# v2_2.net
KiCad netlist of a schematic drawn in EasyEDA Pro
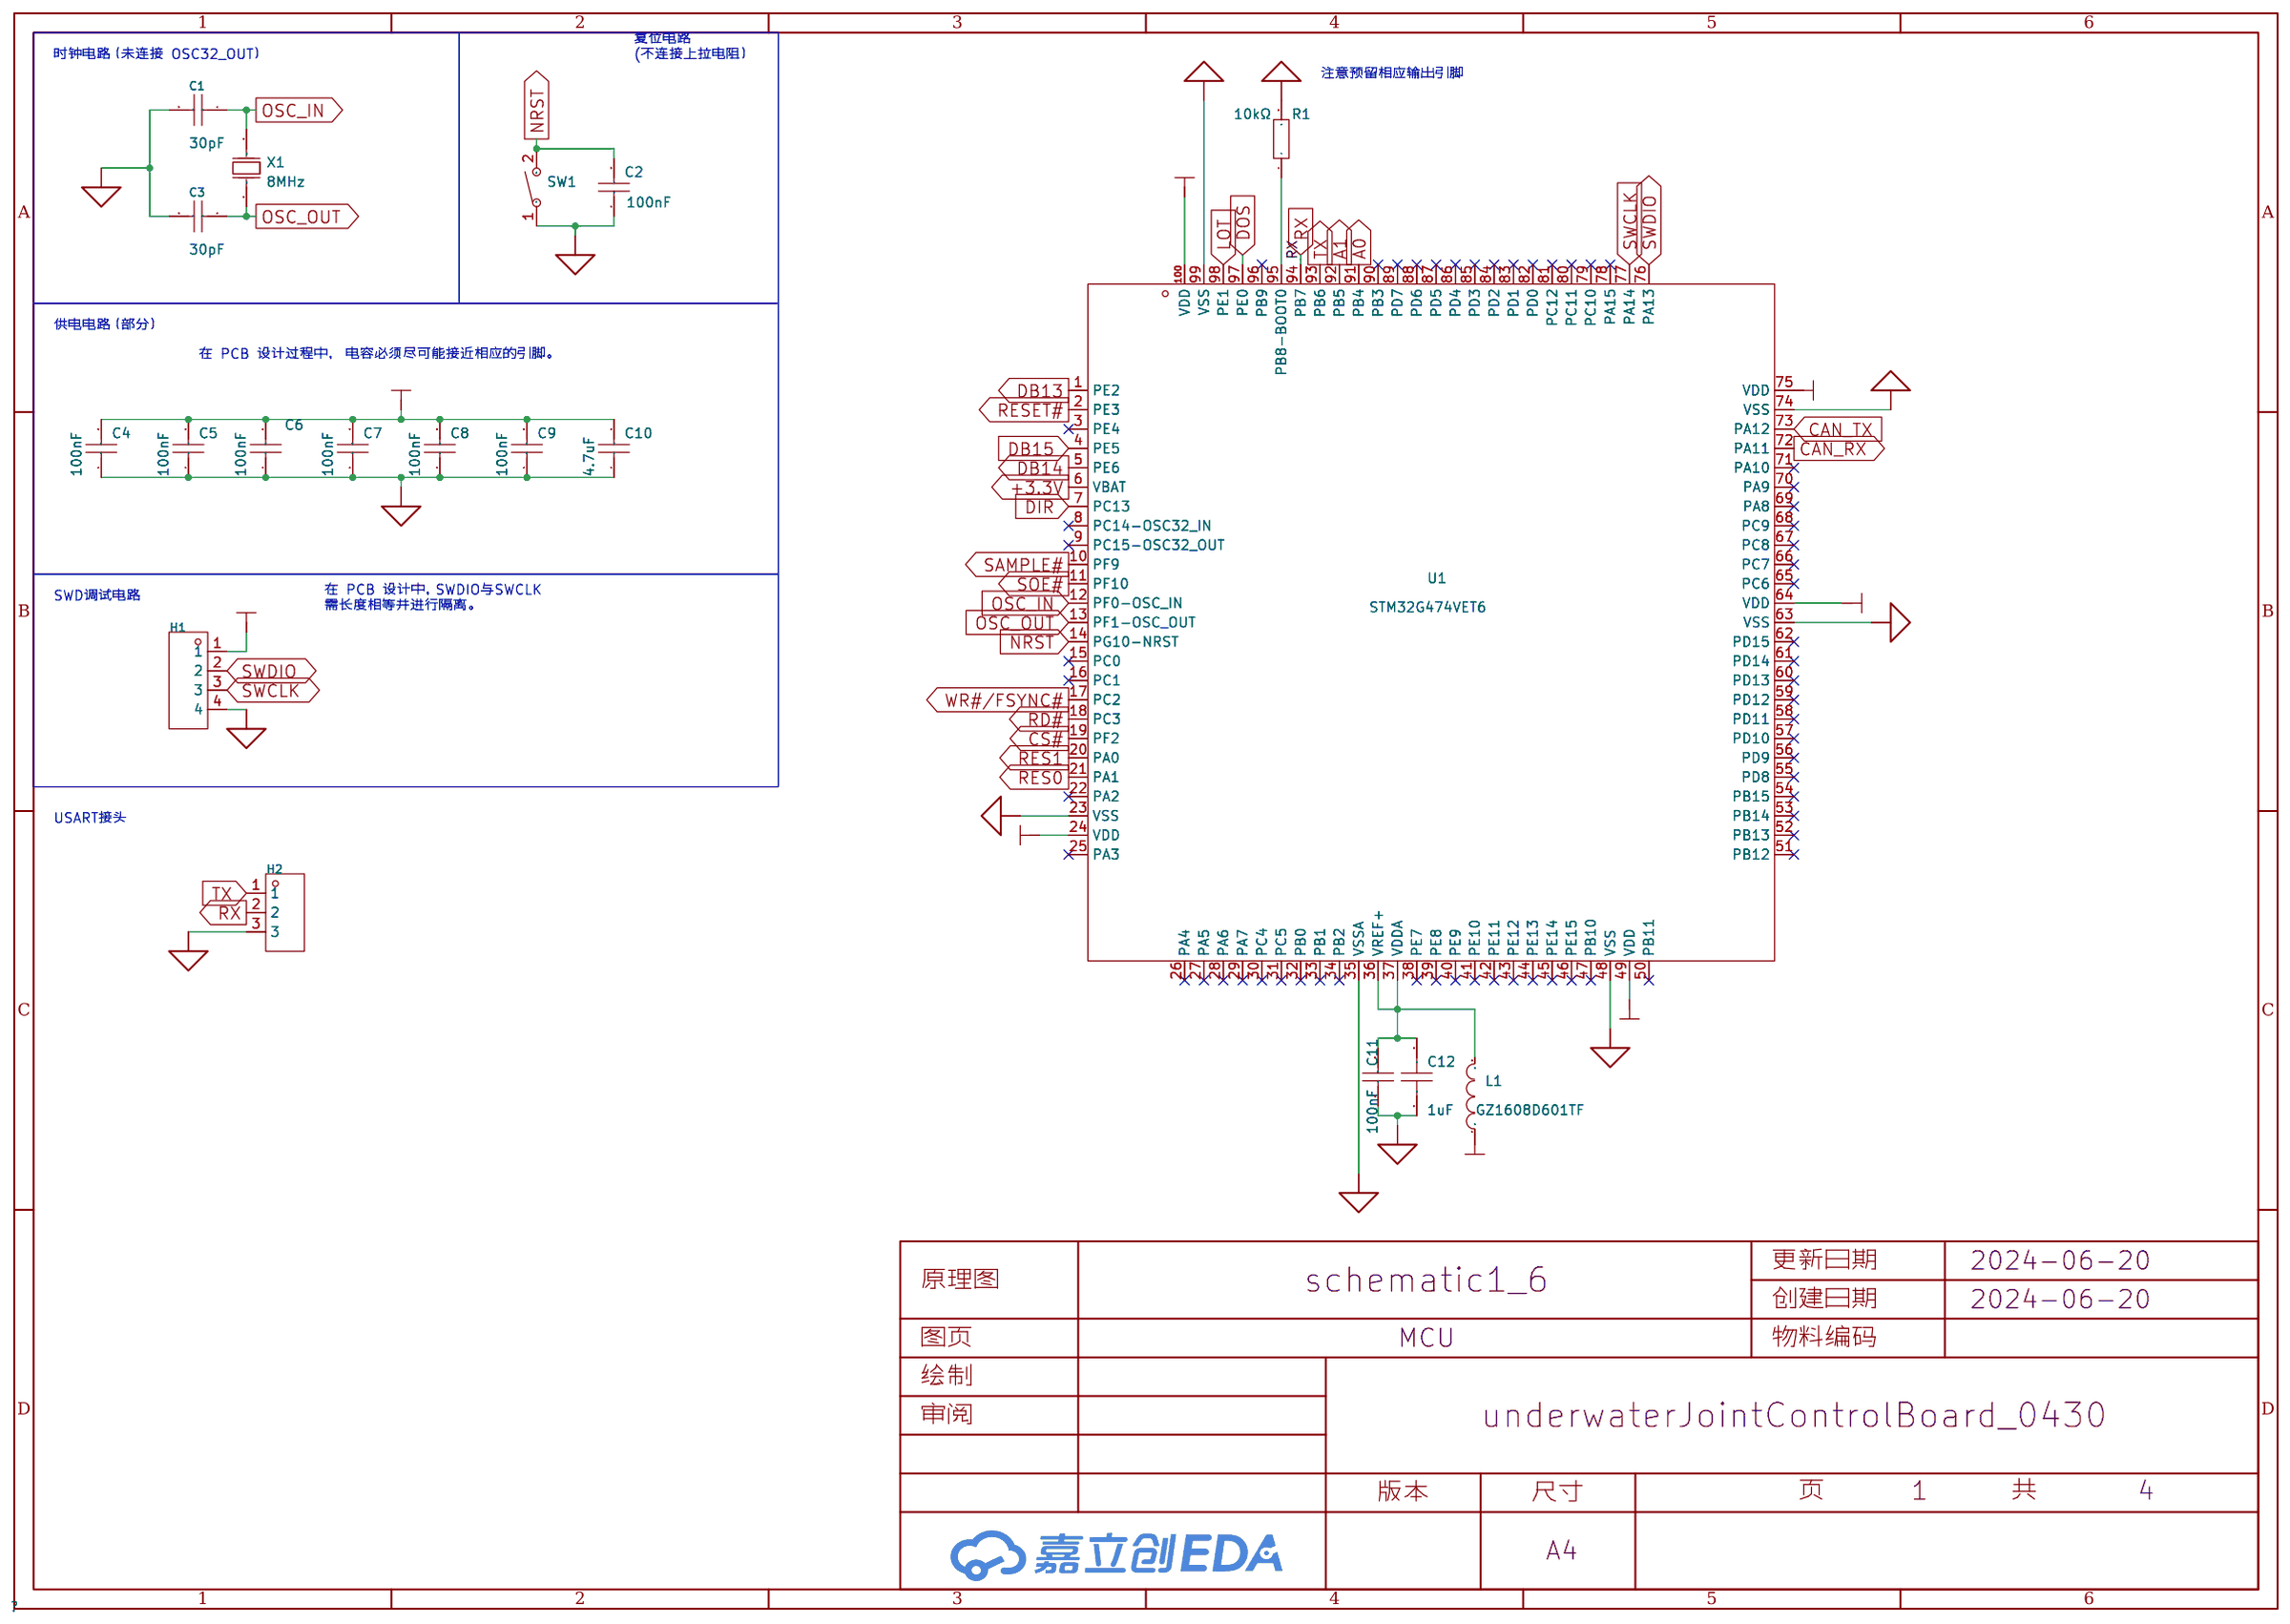
[diagram p0: MCU]
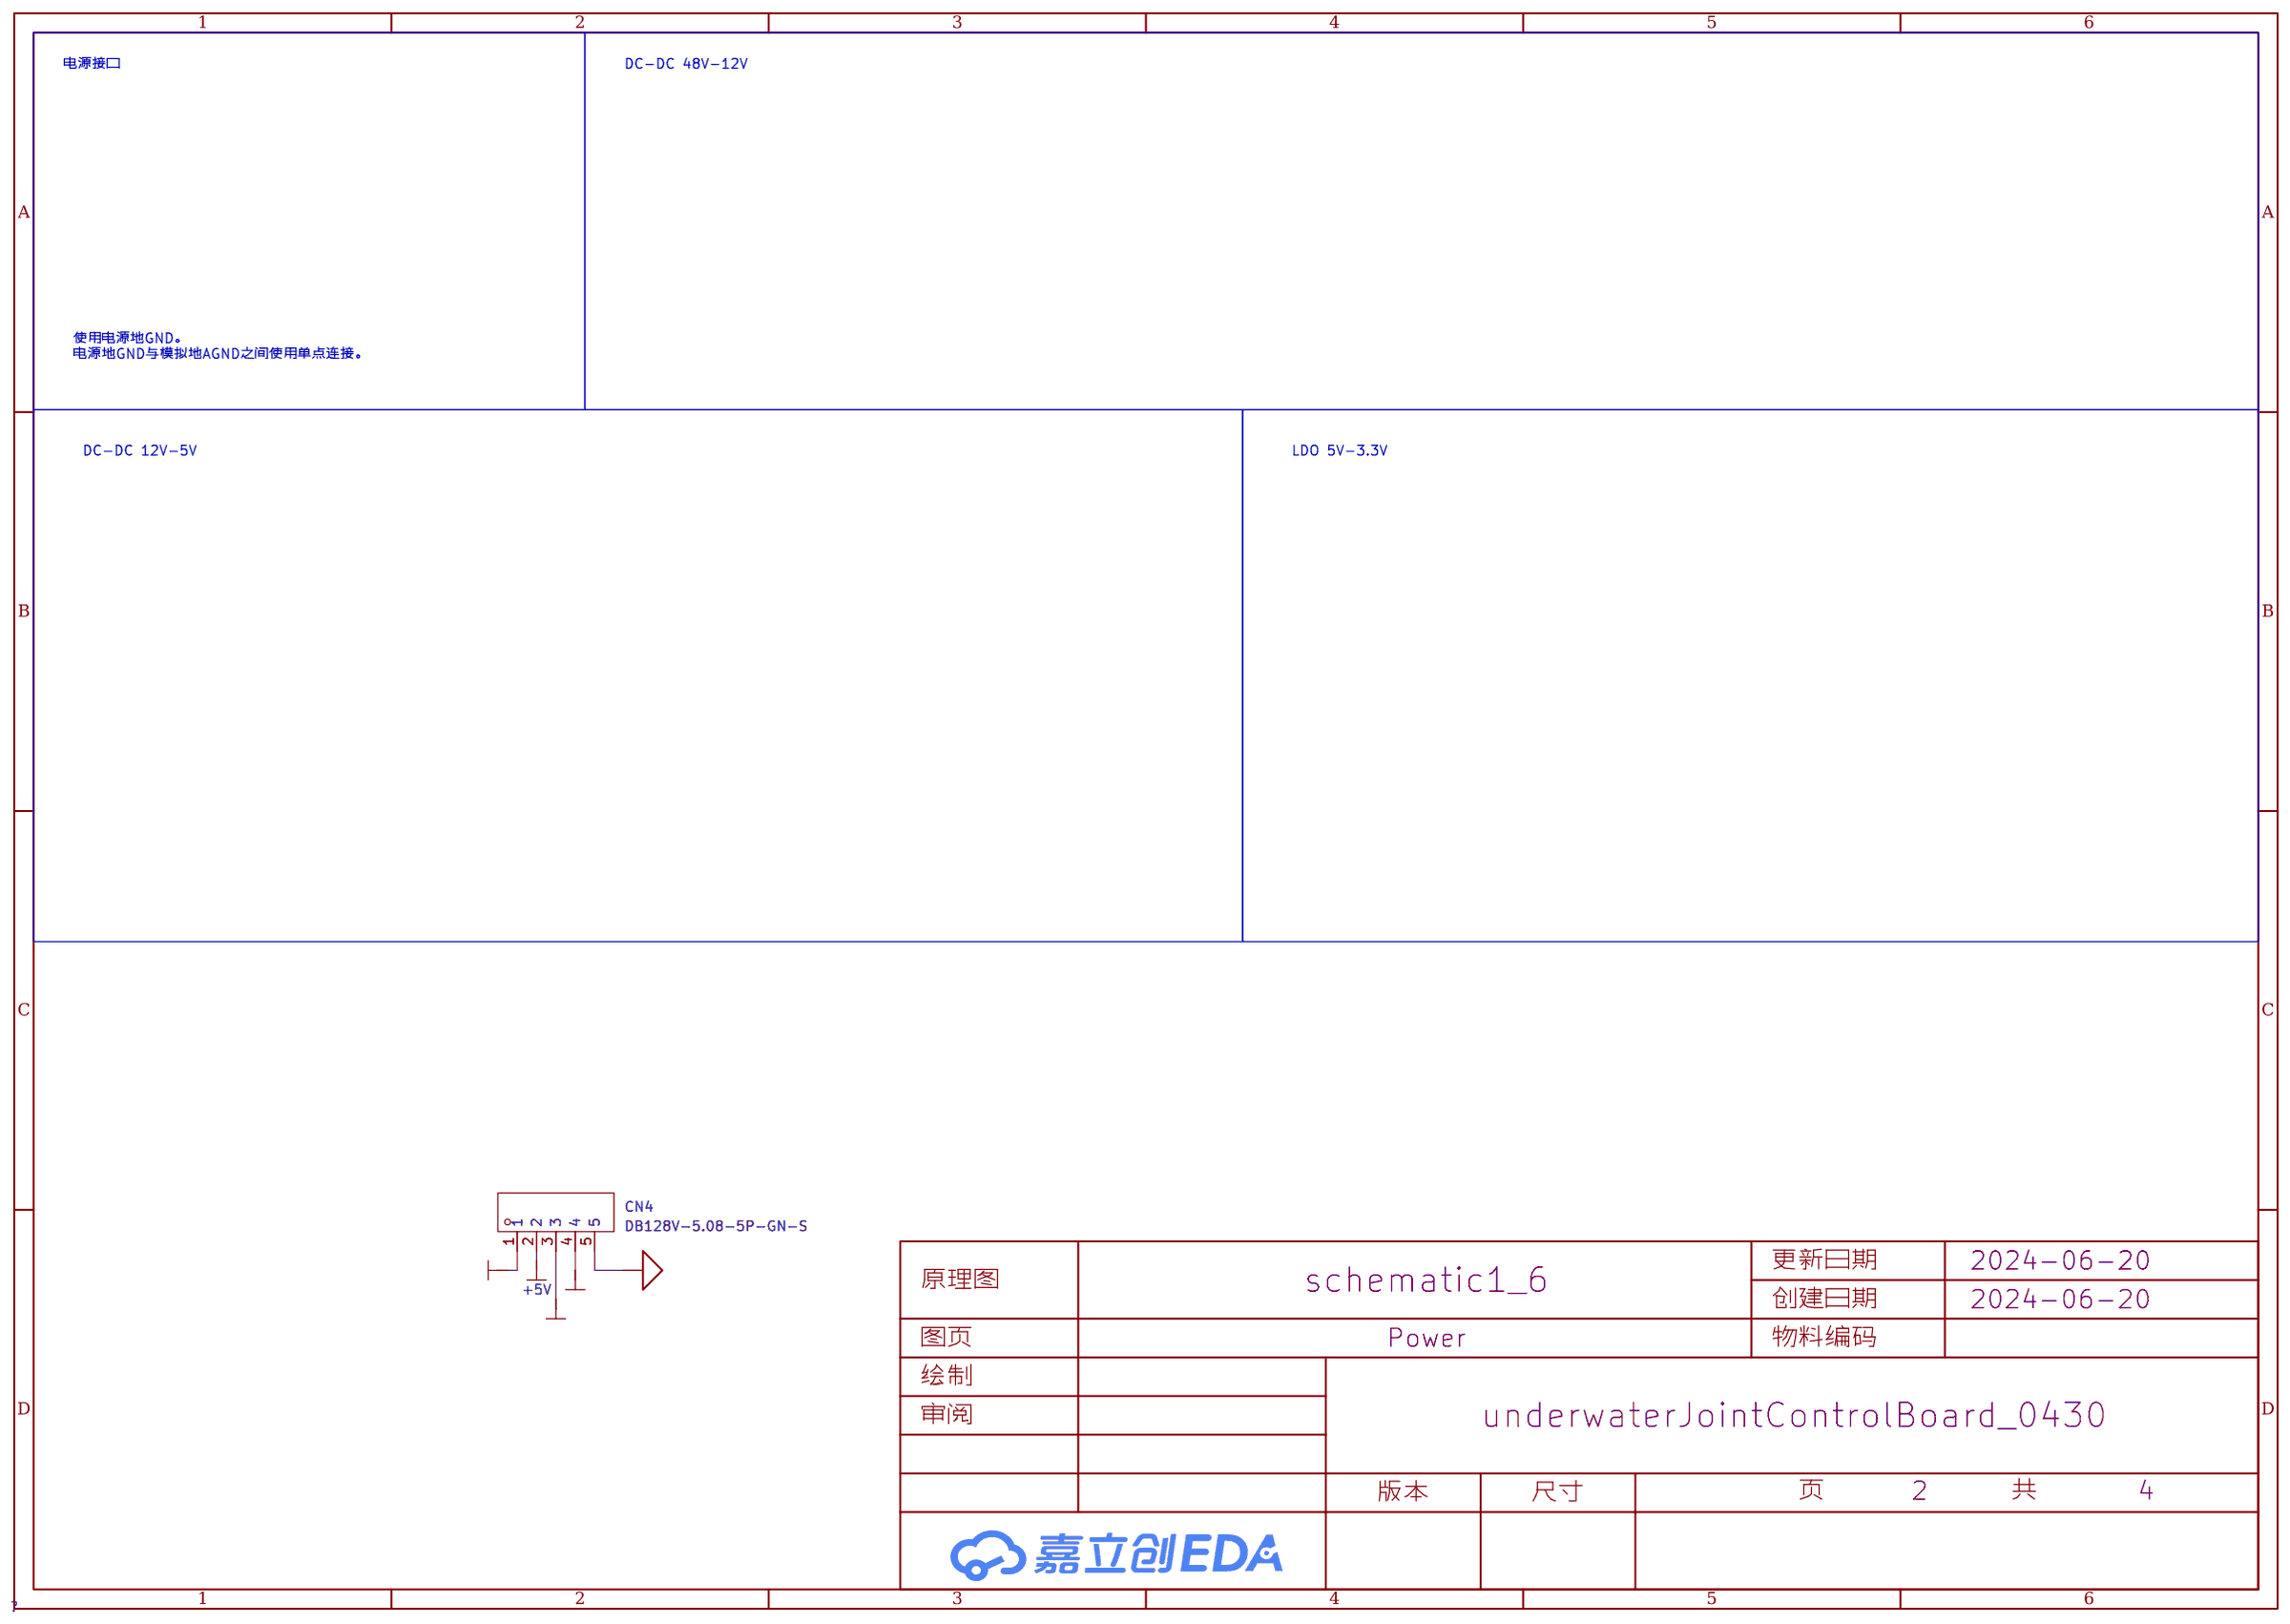
[diagram p1: Power]
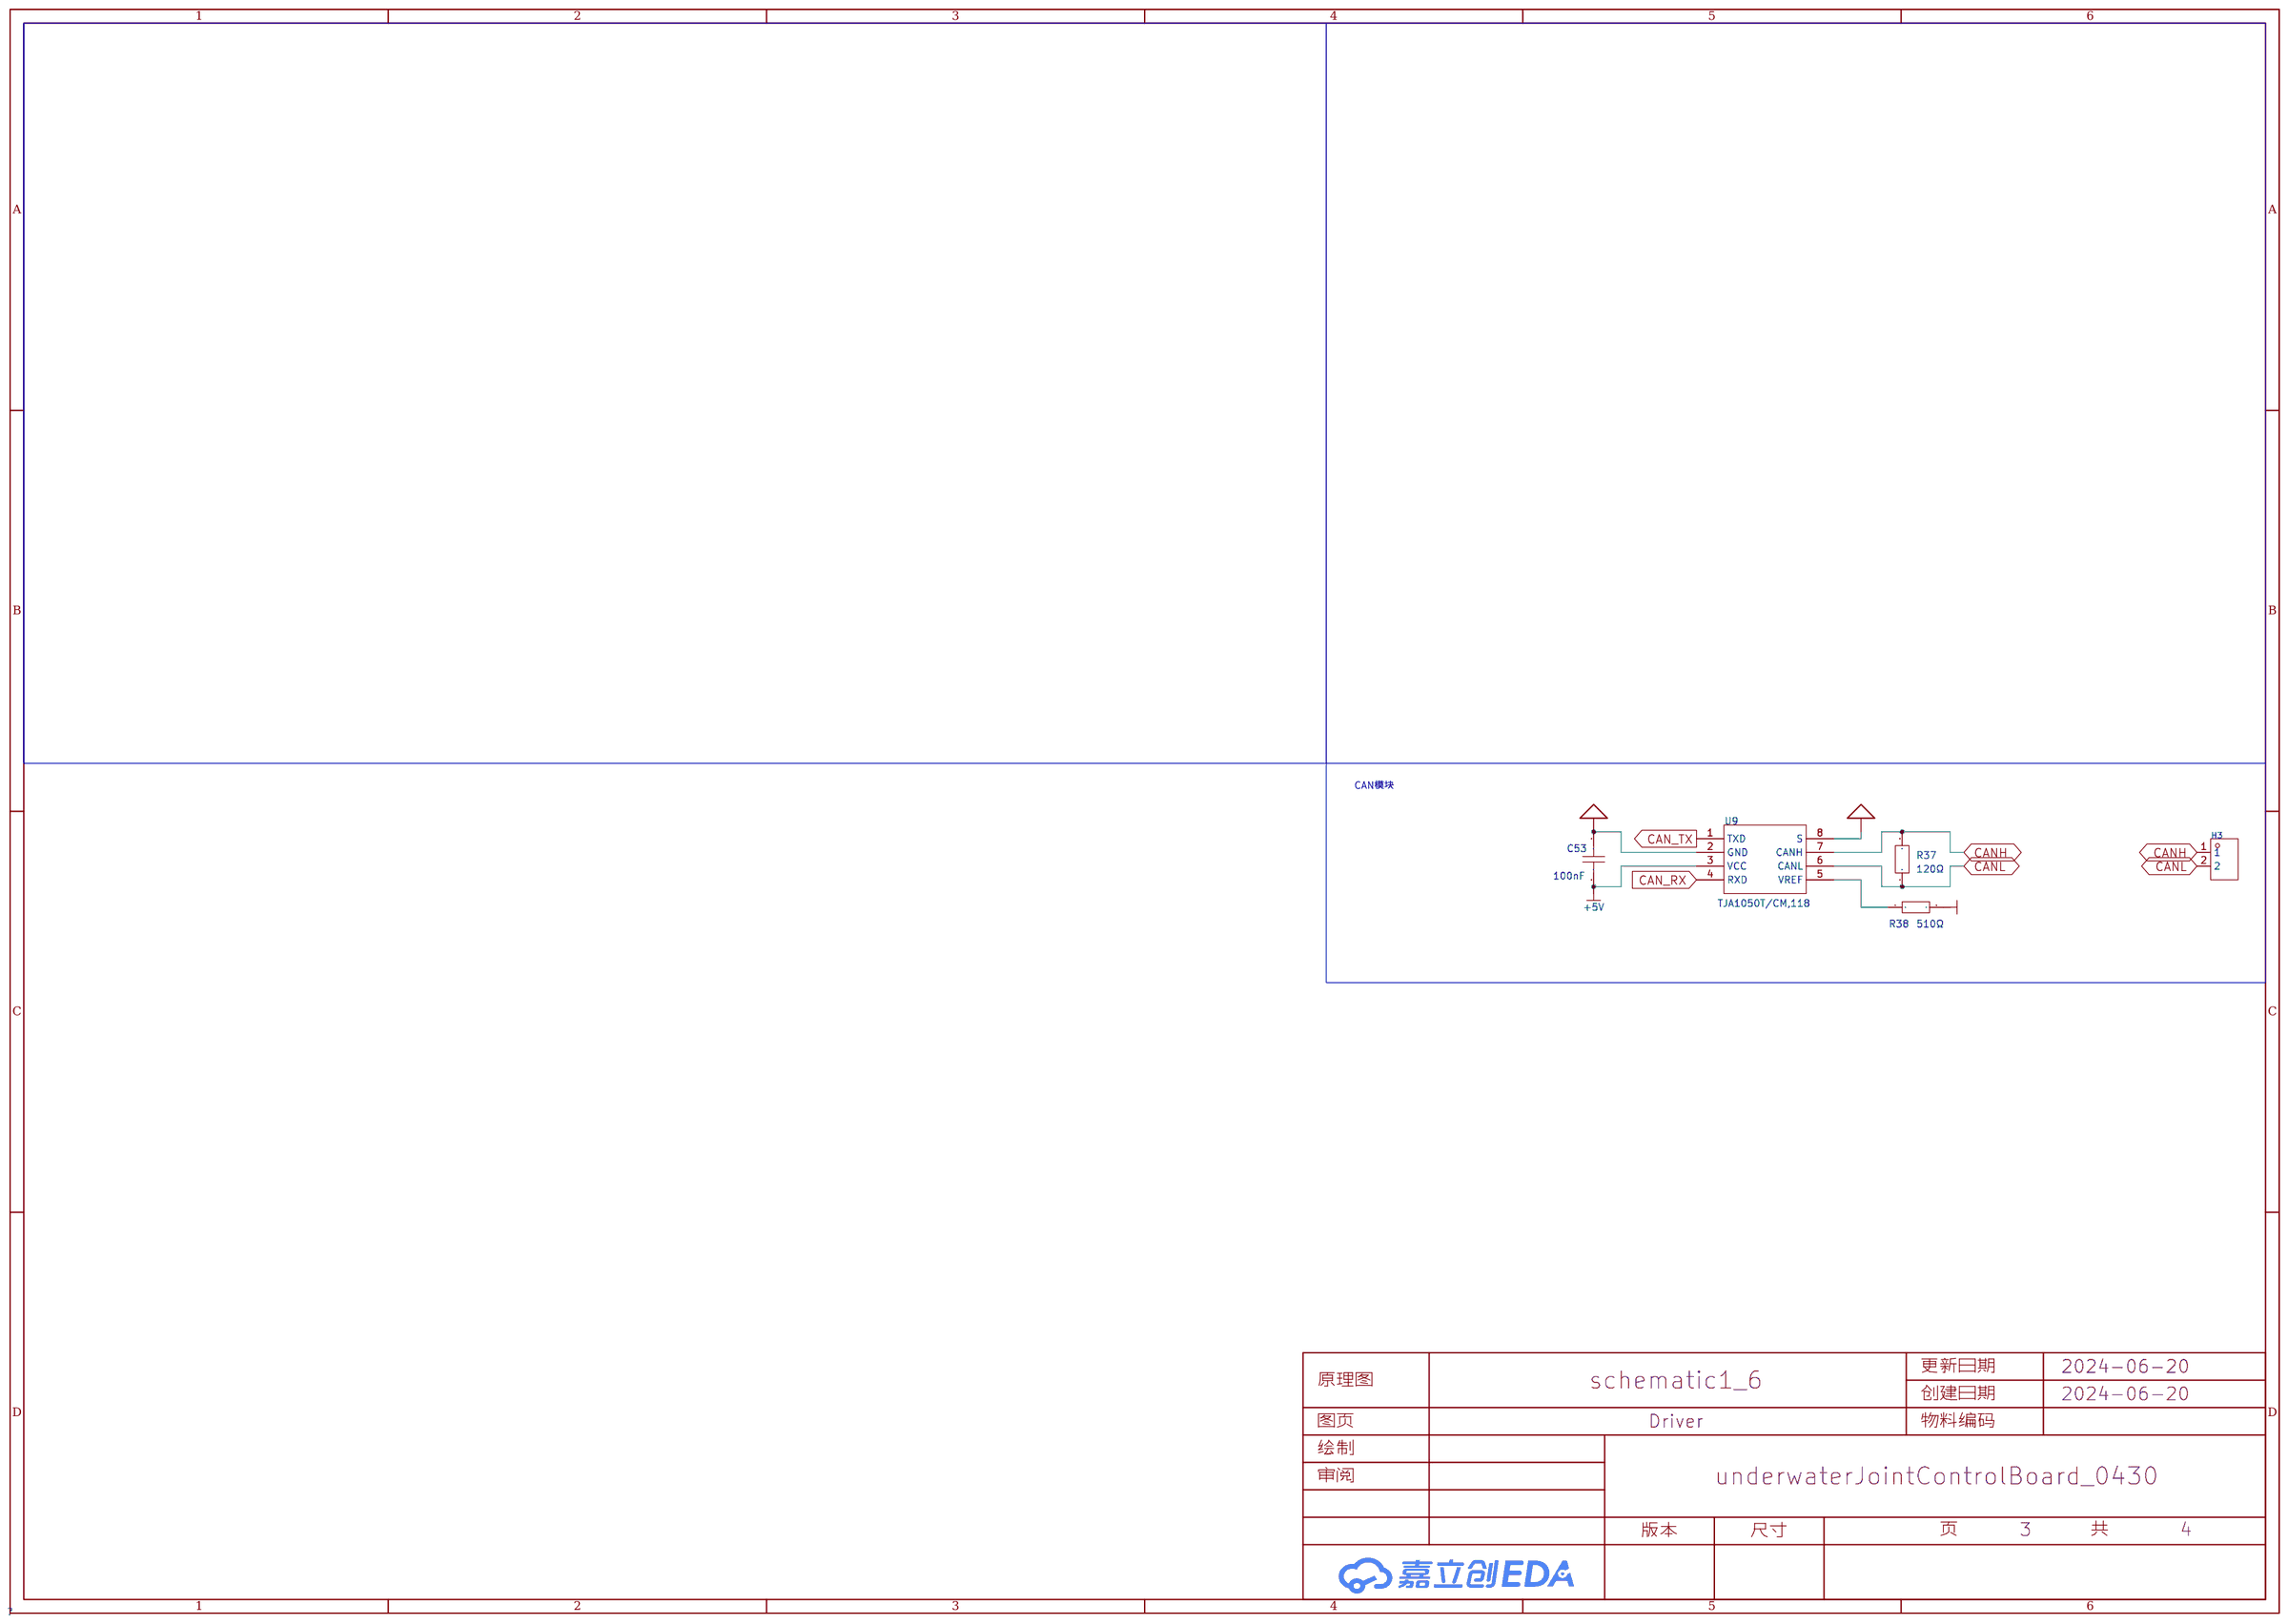
[diagram p2: Driver]
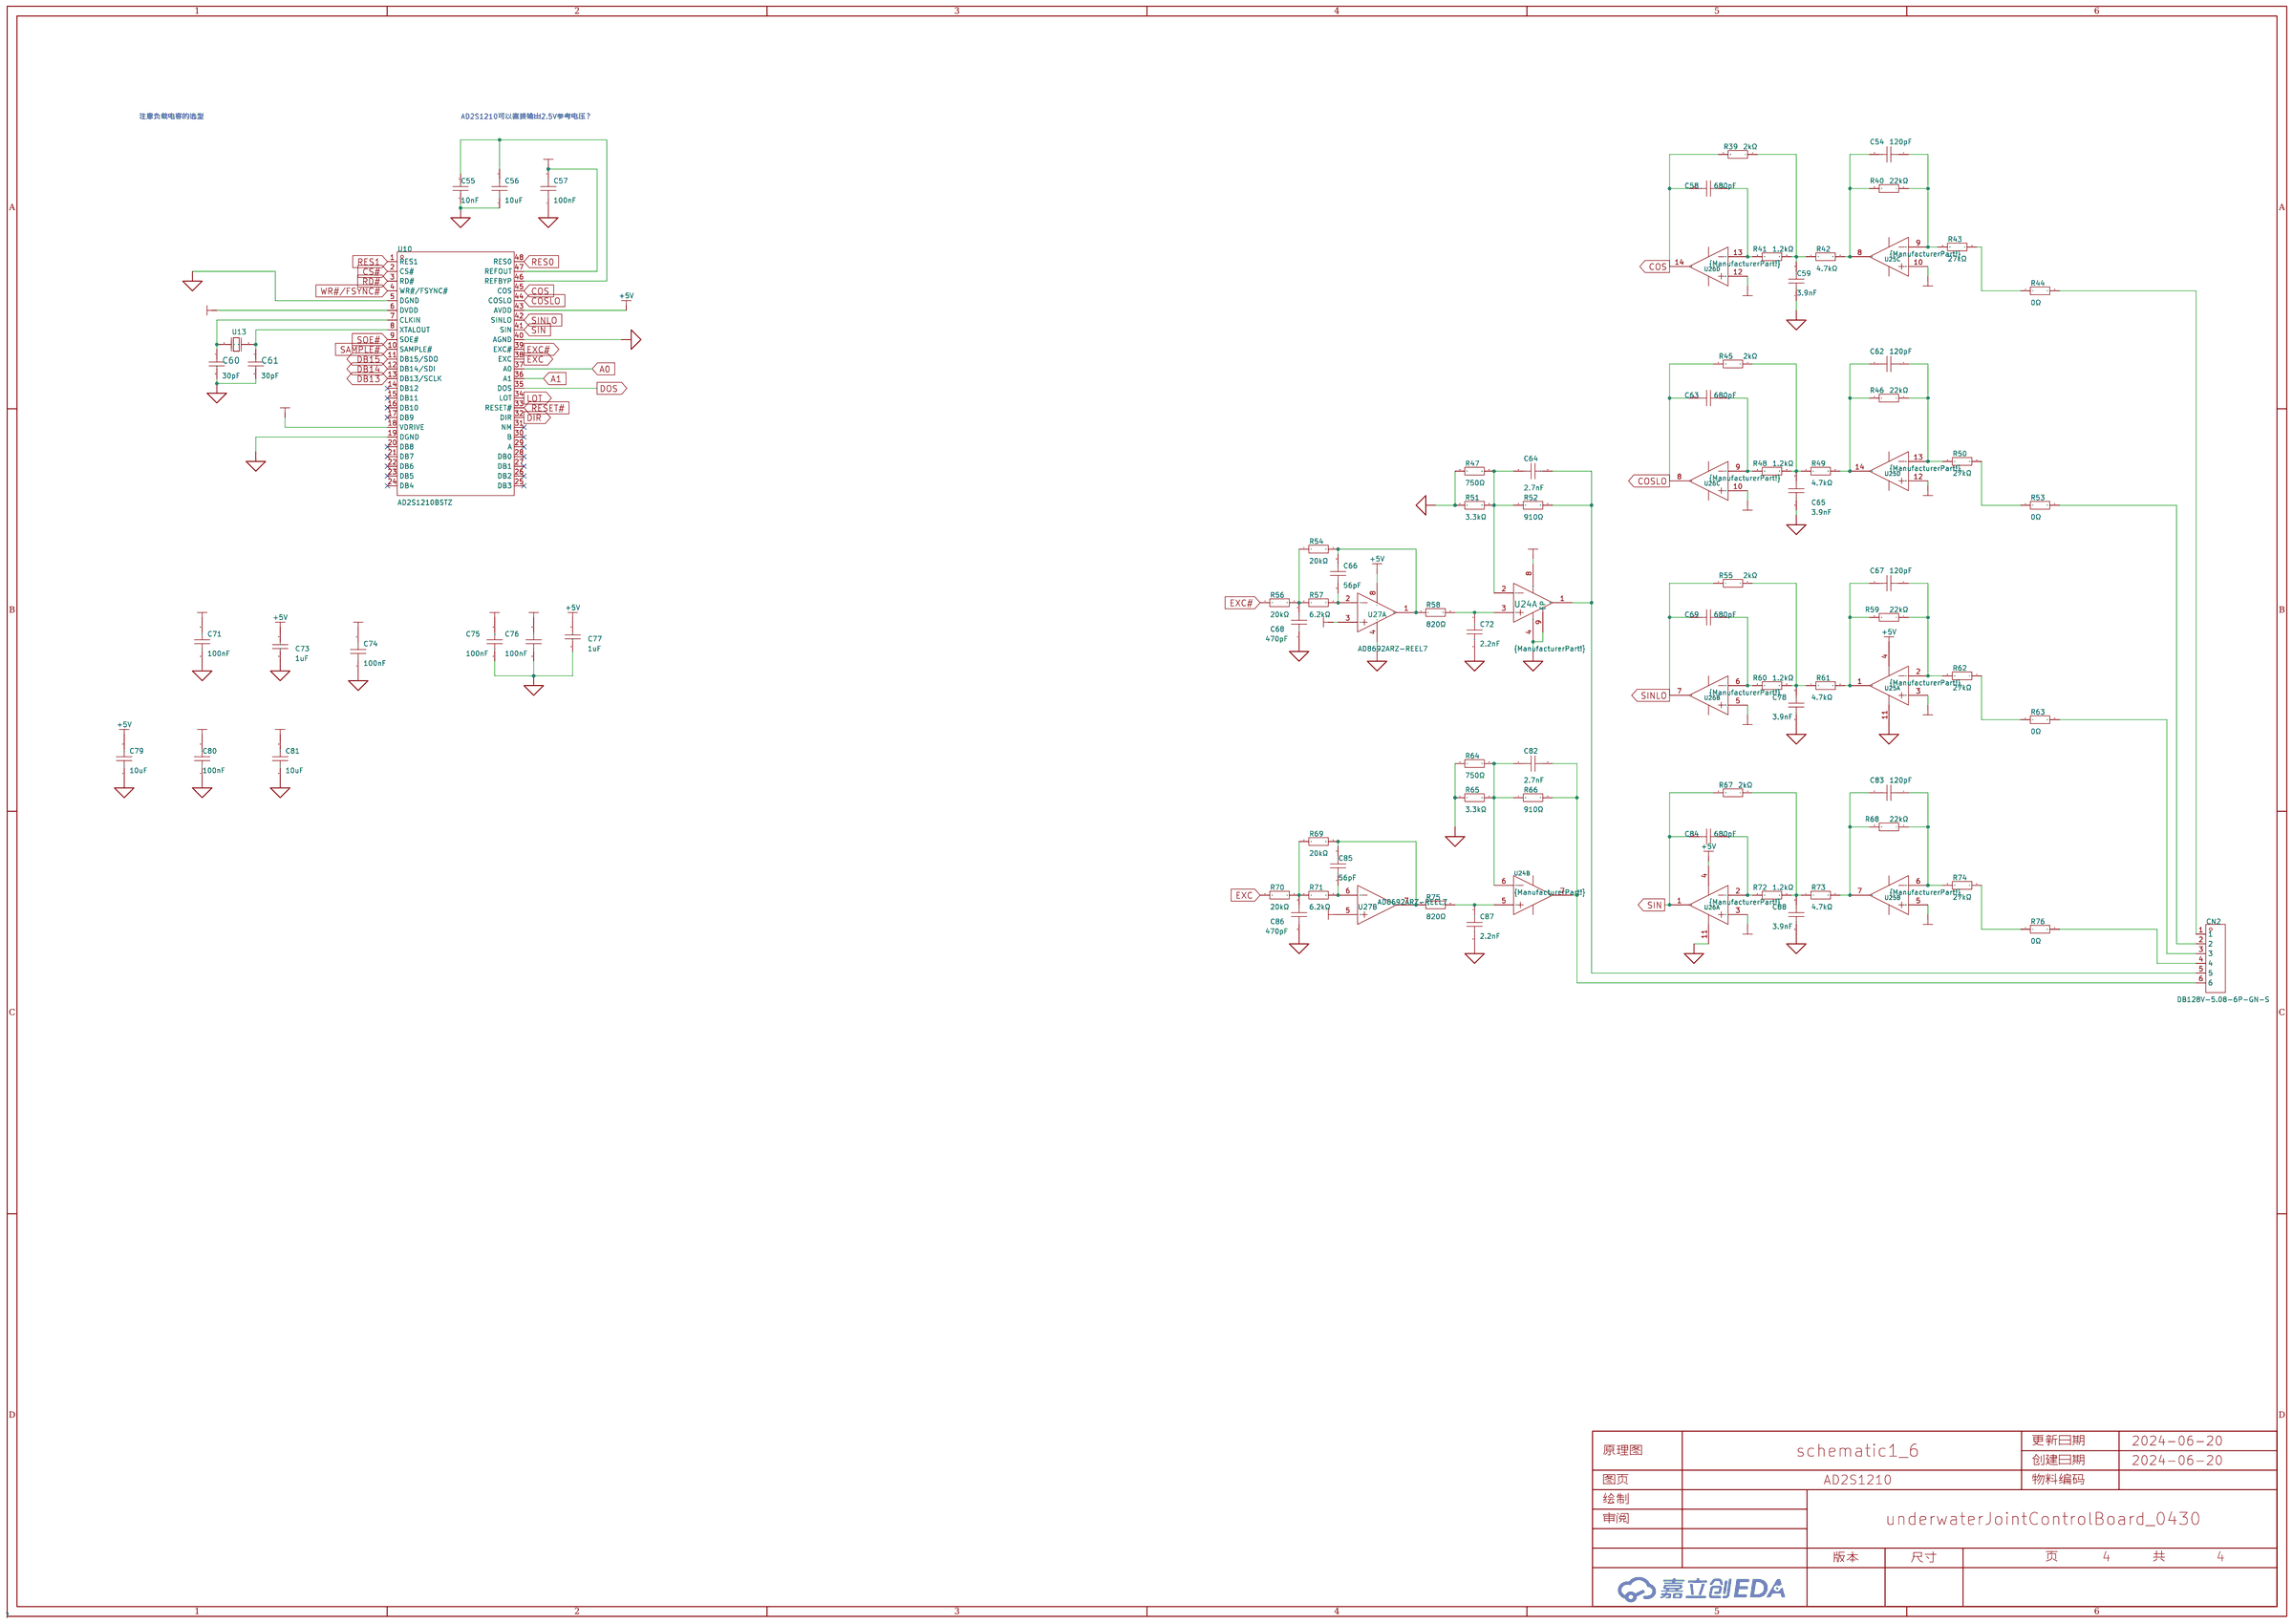
[diagram p3: AD2S1210]

(export (version "E")
  (design (tool "Eeschema 10.0.6"))
  (components
    (comp (ref "C1")
      (value "30pF")
      (footprint "easyedapro:C0402")
      (description "容值:30pF;精度:±5%;额定电压:50V;材质(温度系数):C0G;")
      (fields (field (name "Manufacturer Part") "0402CG300J500NT") (field (name "Manufacturer") "FH(风华)"))
      (libsource (lib "easyedapro") (part "0402CG300J500NT"))
    )
    (comp (ref "C2")
      (value "100nF")
      (footprint "easyedapro:C0402")
      (description "容值:100nF;精度:±10%;额定电压:16V;材质(温度系数):X7R;")
      (fields
        (field (name "Manufacturer Part") "CL05B104KO5NNNC")
        (field (name "Manufacturer") "SAMSUNG(三星)")
      )
      (libsource (lib "easyedapro") (part "CL05B104KO5NNNC"))
    )
    (comp (ref "C3")
      (value "30pF")
      (footprint "easyedapro:C0402")
      (description "容值:30pF;精度:±5%;额定电压:50V;材质(温度系数):C0G;")
      (fields (field (name "Manufacturer Part") "0402CG300J500NT") (field (name "Manufacturer") "FH(风华)"))
      (libsource (lib "easyedapro") (part "0402CG300J500NT"))
    )
    (comp (ref "C4")
      (value "100nF")
      (footprint "easyedapro:C0402")
      (description "容值:100nF;精度:±10%;额定电压:16V;材质(温度系数):X7R;")
      (fields
        (field (name "Manufacturer Part") "CL05B104KO5NNNC")
        (field (name "Manufacturer") "SAMSUNG(三星)")
      )
      (libsource (lib "easyedapro") (part "CL05B104KO5NNNC"))
    )
    (comp (ref "C5")
      (value "100nF")
      (footprint "easyedapro:C0402")
      (description "容值:100nF;精度:±10%;额定电压:16V;材质(温度系数):X7R;")
      (fields
        (field (name "Manufacturer Part") "CL05B104KO5NNNC")
        (field (name "Manufacturer") "SAMSUNG(三星)")
      )
      (libsource (lib "easyedapro") (part "CL05B104KO5NNNC"))
    )
    (comp (ref "C6")
      (value "100nF")
      (footprint "easyedapro:C0402")
      (description "容值:100nF;精度:±10%;额定电压:16V;材质(温度系数):X7R;")
      (fields
        (field (name "Manufacturer Part") "CL05B104KO5NNNC")
        (field (name "Manufacturer") "SAMSUNG(三星)")
      )
      (libsource (lib "easyedapro") (part "CL05B104KO5NNNC"))
    )
    (comp (ref "C7")
      (value "100nF")
      (footprint "easyedapro:C0402")
      (description "容值:100nF;精度:±10%;额定电压:16V;材质(温度系数):X7R;")
      (fields
        (field (name "Manufacturer Part") "CL05B104KO5NNNC")
        (field (name "Manufacturer") "SAMSUNG(三星)")
      )
      (libsource (lib "easyedapro") (part "CL05B104KO5NNNC"))
    )
    (comp (ref "C8")
      (value "100nF")
      (footprint "easyedapro:C0402")
      (description "容值:100nF;精度:±10%;额定电压:16V;材质(温度系数):X7R;")
      (fields
        (field (name "Manufacturer Part") "CL05B104KO5NNNC")
        (field (name "Manufacturer") "SAMSUNG(三星)")
      )
      (libsource (lib "easyedapro") (part "CL05B104KO5NNNC"))
    )
    (comp (ref "C9")
      (value "100nF")
      (footprint "easyedapro:C0402")
      (description "容值:100nF;精度:±10%;额定电压:16V;材质(温度系数):X7R;")
      (fields
        (field (name "Manufacturer Part") "CL05B104KO5NNNC")
        (field (name "Manufacturer") "SAMSUNG(三星)")
      )
      (libsource (lib "easyedapro") (part "CL05B104KO5NNNC"))
    )
    (comp (ref "C10")
      (value "4.7uF")
      (footprint "easyedapro:C0402")
      (description "容值:4.7uF;精度:±20%;额定电压:10V;材质(温度系数):X5R;")
      (fields
        (field (name "Manufacturer Part") "CL05A475MP5NRNC")
        (field (name "Manufacturer") "SAMSUNG(三星)")
      )
      (libsource (lib "easyedapro") (part "CL05A475MP5NRNC"))
    )
    (comp (ref "C11")
      (value "100nF")
      (footprint "easyedapro:C0402")
      (description "容值:100nF;精度:±10%;额定电压:16V;材质(温度系数):X7R;")
      (fields
        (field (name "Manufacturer Part") "CL05B104KO5NNNC")
        (field (name "Manufacturer") "SAMSUNG(三星)")
      )
      (libsource (lib "easyedapro") (part "CL05B104KO5NNNC"))
    )
    (comp (ref "C12")
      (value "1uF")
      (footprint "easyedapro:C0402")
      (description "容值:1uF;精度:±10%;额定电压:25V;材质(温度系数):X5R;")
      (fields
        (field (name "Manufacturer Part") "CL05A105KA5NQNC")
        (field (name "Manufacturer") "SAMSUNG(三星)")
      )
      (libsource (lib "easyedapro") (part "CL05A105KA5NQNC"))
    )
    (comp (ref "H1")
      (value "PZ254V-11-04P")
      (footprint "easyedapro:HDR-TH_4P-P2.54-V-M")
      (fields (field (name "Manufacturer") "XFCN(兴飞)"))
      (libsource (lib "easyedapro") (part "PZ254V-11-04P_C2691448"))
    )
    (comp (ref "H2")
      (value "PZ254V-11-03P")
      (footprint "easyedapro:HDR-TH_3P-P2.54-V-M")
      (fields (field (name "Manufacturer") "XFCN(兴飞)"))
      (libsource (lib "easyedapro") (part "PZ254V-11-03P_C2937625"))
    )
    (comp (ref "L1")
      (value "GZ1608D601TF")
      (footprint "easyedapro:L0603")
      (description "标称阻抗@测试频率:600Ω@100MHz;误差:±25%;直流电阻(RDC):450mΩ;")
      (fields (field (name "Manufacturer") "Sunlord(顺络)"))
      (libsource (lib "easyedapro") (part "GZ1608D601TF"))
    )
    (comp (ref "R1")
      (value "10kΩ")
      (footprint "easyedapro:R0402")
      (description "阻值:10kΩ;精度:±1%;功率:62.5mW;温度系数:±100ppm/°C;电阻类型:厚膜电阻;")
      (fields
        (field (name "Manufacturer Part") "0402WGF1002TCE")
        (field (name "Manufacturer") "UNI-ROYAL(厚声)")
      )
      (libsource (lib "easyedapro") (part "0402WGF1002TCE"))
    )
    (comp (ref "SW1")
      (value "TS-1185-B-B-B-A")
      (footprint "easyedapro:SW-SMD_L4.0-W3.0-LS5.0")
      (description "触点电流:50mA;额定电压(DC):12V;绝缘电阻:-;电路结构:单刀单掷;安装方式:立贴;带灯:无;作用力:160gf;机械寿命:10万次;带支架:否;")
      (fields (field (name "Manufacturer") "XKB Connectivity(中国星坤)"))
      (libsource (lib "easyedapro") (part "TS-1185-B-B-B-A"))
    )
    (comp (ref "U1")
      (value "STM32G474VET6")
      (footprint "easyedapro:LQFP-100_L14.0-W14.0-P0.50-LS16.0-BL")
      (fields (field (name "Manufacturer") "ST(意法半导体)"))
      (libsource (lib "easyedapro") (part "STM32G474VET6"))
    )
    (comp (ref "X1")
      (value "8MHz")
      (footprint "easyedapro:CRYSTAL-SMD_L5.0-W3.2")
      (description "频率:8MHz;负载电容:20pF;频率公差:±10ppm;")
      (fields (field (name "Manufacturer Part") "X50328MSB2GI") (field (name "Manufacturer") "YXC(扬兴晶振)"))
      (libsource (lib "easyedapro") (part "X50328MSB2GI"))
    )
    (comp (ref "CN4")
      (value "DB128V-5.08-5P-GN-S")
      (footprint "easyedapro:CONN-TH_5P-P5.08_DIBO_DB128V-5.08-5P-GN-S")
      (fields (field (name "Manufacturer") "DORABO(地博电气)"))
      (libsource (lib "easyedapro") (part "DB128V-5.08-5P-GN-S"))
    )
    (comp (ref "C53")
      (value "100nF")
      (footprint "easyedapro:C0603")
      (description "容值:100nF;精度:±10%;额定电压:50V;材质(温度系数):X7R;")
      (fields
        (field (name "Manufacturer Part") "CC0603KRX7R9BB104")
        (field (name "Manufacturer") "YAGEO(国巨)")
      )
      (libsource (lib "easyedapro") (part "CC0603KRX7R9BB104"))
    )
    (comp (ref "H3")
      (value "PZ254V-11-02P")
      (footprint "easyedapro:HDR-TH_2P-P2.54-V-M")
      (fields (field (name "Manufacturer") "XFCN(兴飞)"))
      (libsource (lib "easyedapro") (part "PZ254V-11-02P"))
    )
    (comp (ref "R37")
      (value "120Ω")
      (footprint "easyedapro:R0603")
      (description "阻值:120Ω;精度:±5%;功率:250mW;温度系数:±200ppm/°C;电阻类型:厚膜电阻;")
      (fields (field (name "Manufacturer Part") "ERJPA3J121V") (field (name "Manufacturer") "PANASONIC(松下)"))
      (libsource (lib "easyedapro") (part "ERJPA3J121V"))
    )
    (comp (ref "R38")
      (value "510Ω")
      (footprint "easyedapro:R0402")
      (description "阻值:510Ω;精度:±1%;功率:62.5mW;温度系数:±100ppm/°C;电阻类型:厚膜电阻;")
      (fields
        (field (name "Manufacturer Part") "0402WGF5100TCE")
        (field (name "Manufacturer") "UNI-ROYAL(厚声)")
      )
      (libsource (lib "easyedapro") (part "0402WGF5100TCE"))
    )
    (comp (ref "U9")
      (value "TJA1050T/CM,118")
      (footprint "easyedapro:SOIC-8_L5.0-W4.0-P1.27-LS6.0-BL")
      (description "类型:收发器;")
      (fields (field (name "Manufacturer") "NXP(恩智浦)"))
      (libsource (lib "easyedapro") (part "TJA1050T/CM,118"))
    )
    (comp (ref "C54")
      (value "120pF")
      (fields
        (field (name "Manufacturer Part") "CC0603JRNPO0BN121")
        (field (name "Manufacturer") "YAGEO(国巨)")
      )
      (libsource (lib "easyedapro") (part "tcc0402cog121j500at"))
    )
    (comp (ref "C55")
      (value "10nF")
      (footprint "easyedapro:C0603")
      (description "容值:10nF;精度:±10%;额定电压:100V;材质(温度系数):X7R;")
      (fields
        (field (name "Manufacturer Part") "CC0603KRX7R0BB103")
        (field (name "Manufacturer") "YAGEO(国巨)")
      )
      (libsource (lib "easyedapro") (part "CC0603KRX7R0BB103"))
    )
    (comp (ref "C56")
      (value "10uF")
      (footprint "easyedapro:C0805")
      (description "容值:10uF;精度:±10%;额定电压:50V;材质(温度系数):X5R;")
      (fields
        (field (name "Manufacturer Part") "GRM21BR61H106KE43L")
        (field (name "Manufacturer") "muRata(村田)")
      )
      (libsource (lib "easyedapro") (part "GRM21BR61H106KE43L"))
    )
    (comp (ref "C57")
      (value "100nF")
      (footprint "easyedapro:C0805")
      (description "容值:100nF;精度:±10%;额定电压:25V;材质(温度系数):X7R;")
      (fields
        (field (name "Manufacturer Part") "CC0805KRX7R8BB104")
        (field (name "Manufacturer") "YAGEO(国巨)")
      )
      (libsource (lib "easyedapro") (part "CC0805KRX7R8BB104"))
    )
    (comp (ref "C58")
      (value "680pF")
      (footprint "easyedapro:C0603")
      (description "容值:680pF;精度:±1%;额定电压:50V;材质(温度系数):NP0;")
      (fields
        (field (name "Manufacturer Part") "CC0603FRNPO9BN681")
        (field (name "Manufacturer") "YAGEO(国巨)")
      )
      (libsource (lib "easyedapro") (part "CC0603FRNPO9BN681"))
    )
    (comp (ref "C59")
      (value "3.9nF")
      (footprint "easyedapro:C0805")
      (description "容值:3.9nF;精度:±1%;额定电压:50V;材质(温度系数):NP0;")
      (fields
        (field (name "Manufacturer Part") "CC0805FKNPO9BN392")
        (field (name "Manufacturer") "YAGEO(国巨)")
      )
      (libsource (lib "easyedapro") (part "CC0805FKNPO9BN392"))
    )
    (comp (ref "C60")
      (value "30pF")
      (footprint "easyedapro:C0402")
      (description "容值:30pF;精度:±5%;额定电压:50V;材质(温度系数):C0G;")
      (fields (field (name "Manufacturer Part") "0402CG300J500NT") (field (name "Manufacturer") "FH(风华)"))
      (libsource (lib "easyedapro") (part "0402CG300J500NT"))
    )
    (comp (ref "C61")
      (value "30pF")
      (footprint "easyedapro:C0402")
      (description "容值:30pF;精度:±5%;额定电压:50V;材质(温度系数):C0G;")
      (fields (field (name "Manufacturer Part") "0402CG300J500NT") (field (name "Manufacturer") "FH(风华)"))
      (libsource (lib "easyedapro") (part "0402CG300J500NT"))
    )
    (comp (ref "C62")
      (value "120pF")
      (fields
        (field (name "Manufacturer Part") "CC0603JRNPO0BN121")
        (field (name "Manufacturer") "YAGEO(国巨)")
      )
      (libsource (lib "easyedapro") (part "tcc0402cog121j500at"))
    )
    (comp (ref "C63")
      (value "680pF")
      (footprint "easyedapro:C0603")
      (description "容值:680pF;精度:±1%;额定电压:50V;材质(温度系数):NP0;")
      (fields
        (field (name "Manufacturer Part") "CC0603FRNPO9BN681")
        (field (name "Manufacturer") "YAGEO(国巨)")
      )
      (libsource (lib "easyedapro") (part "CC0603FRNPO9BN681"))
    )
    (comp (ref "C64")
      (value "2.7nF")
      (footprint "easyedapro:C0603")
      (description "容值:2.7nF;精度:±5%;额定电压:50V;材质(温度系数):NP0;")
      (fields
        (field (name "Manufacturer Part") "CC0603JRNPO9BN272")
        (field (name "Manufacturer") "YAGEO(国巨)")
      )
      (libsource (lib "easyedapro") (part "CC0603JRNPO9BN272"))
    )
    (comp (ref "C65")
      (value "3.9nF")
      (footprint "easyedapro:C0805")
      (description "容值:3.9nF;精度:±1%;额定电压:50V;材质(温度系数):NP0;")
      (fields
        (field (name "Manufacturer Part") "CC0805FKNPO9BN392")
        (field (name "Manufacturer") "YAGEO(国巨)")
      )
      (libsource (lib "easyedapro") (part "CC0805FKNPO9BN392"))
    )
    (comp (ref "C66")
      (value "56pF")
      (footprint "easyedapro:C0805")
      (description "容值:56pF;精度:±5%;额定电压:200V;材质(温度系数):NP0;")
      (fields
        (field (name "Manufacturer Part") "CC0805JRNPOABN560")
        (field (name "Manufacturer") "YAGEO(国巨)")
      )
      (libsource (lib "easyedapro") (part "CC0805JRNPOABN560"))
    )
    (comp (ref "C67")
      (value "120pF")
      (fields
        (field (name "Manufacturer Part") "CC0603JRNPO0BN121")
        (field (name "Manufacturer") "YAGEO(国巨)")
      )
      (libsource (lib "easyedapro") (part "tcc0402cog121j500at"))
    )
    (comp (ref "C68")
      (value "470pF")
      (fields (field (name "Manufacturer Part") "0805B471K101CT") (field (name "Manufacturer") "Walsin(华新科)"))
      (libsource (lib "easyedapro") (part "tcc1206x7r471k102dts"))
    )
    (comp (ref "C69")
      (value "680pF")
      (footprint "easyedapro:C0603")
      (description "容值:680pF;精度:±1%;额定电压:50V;材质(温度系数):NP0;")
      (fields
        (field (name "Manufacturer Part") "CC0603FRNPO9BN681")
        (field (name "Manufacturer") "YAGEO(国巨)")
      )
      (libsource (lib "easyedapro") (part "CC0603FRNPO9BN681"))
    )
    (comp (ref "C71")
      (value "100nF")
      (footprint "easyedapro:C0805")
      (description "容值:100nF;精度:±10%;额定电压:25V;材质(温度系数):X7R;")
      (fields
        (field (name "Manufacturer Part") "CC0805KRX7R8BB104")
        (field (name "Manufacturer") "YAGEO(国巨)")
      )
      (libsource (lib "easyedapro") (part "CC0805KRX7R8BB104"))
    )
    (comp (ref "C72")
      (value "2.2nF")
      (fields
        (field (name "Manufacturer Part") "CL21C222JBFNNNE")
        (field (name "Manufacturer") "SAMSUNG(三星)")
      )
      (libsource (lib "easyedapro") (part "tcc1206x7r222k102dts"))
    )
    (comp (ref "C73")
      (value "1uF")
      (footprint "easyedapro:C0402")
      (description "容值:1uF;精度:±10%;额定电压:10V;材质(温度系数):X5R;")
      (fields
        (field (name "Manufacturer Part") "CL05A105KP5NNNC")
        (field (name "Manufacturer") "SAMSUNG(三星)")
      )
      (libsource (lib "easyedapro") (part "CL05A105KP5NNNC"))
    )
    (comp (ref "C74")
      (value "100nF")
      (footprint "easyedapro:C0805")
      (description "容值:100nF;精度:±10%;额定电压:25V;材质(温度系数):X7R;")
      (fields
        (field (name "Manufacturer Part") "CC0805KRX7R8BB104")
        (field (name "Manufacturer") "YAGEO(国巨)")
      )
      (libsource (lib "easyedapro") (part "CC0805KRX7R8BB104"))
    )
    (comp (ref "C75")
      (value "100nF")
      (footprint "easyedapro:C0805")
      (description "容值:100nF;精度:±10%;额定电压:25V;材质(温度系数):X7R;")
      (fields
        (field (name "Manufacturer Part") "CC0805KRX7R8BB104")
        (field (name "Manufacturer") "YAGEO(国巨)")
      )
      (libsource (lib "easyedapro") (part "CC0805KRX7R8BB104"))
    )
    (comp (ref "C76")
      (value "100nF")
      (footprint "easyedapro:C0805")
      (description "容值:100nF;精度:±10%;额定电压:25V;材质(温度系数):X7R;")
      (fields
        (field (name "Manufacturer Part") "CC0805KRX7R8BB104")
        (field (name "Manufacturer") "YAGEO(国巨)")
      )
      (libsource (lib "easyedapro") (part "CC0805KRX7R8BB104"))
    )
    (comp (ref "C77")
      (value "1uF")
      (footprint "easyedapro:C0402")
      (description "容值:1uF;精度:±10%;额定电压:10V;材质(温度系数):X5R;")
      (fields
        (field (name "Manufacturer Part") "CL05A105KP5NNNC")
        (field (name "Manufacturer") "SAMSUNG(三星)")
      )
      (libsource (lib "easyedapro") (part "CL05A105KP5NNNC"))
    )
    (comp (ref "C78")
      (value "3.9nF")
      (footprint "easyedapro:C0805")
      (description "容值:3.9nF;精度:±1%;额定电压:50V;材质(温度系数):NP0;")
      (fields
        (field (name "Manufacturer Part") "CC0805FKNPO9BN392")
        (field (name "Manufacturer") "YAGEO(国巨)")
      )
      (libsource (lib "easyedapro") (part "CC0805FKNPO9BN392"))
    )
    (comp (ref "C79")
      (value "10uF")
      (footprint "easyedapro:C0805")
      (description "容值:10uF;精度:±10%;额定电压:50V;材质(温度系数):X5R;")
      (fields
        (field (name "Manufacturer Part") "GRM21BR61H106KE43L")
        (field (name "Manufacturer") "muRata(村田)")
      )
      (libsource (lib "easyedapro") (part "GRM21BR61H106KE43L"))
    )
    (comp (ref "C80")
      (value "100nF")
      (footprint "easyedapro:C0805")
      (description "容值:100nF;精度:±10%;额定电压:25V;材质(温度系数):X7R;")
      (fields
        (field (name "Manufacturer Part") "CC0805KRX7R8BB104")
        (field (name "Manufacturer") "YAGEO(国巨)")
      )
      (libsource (lib "easyedapro") (part "CC0805KRX7R8BB104"))
    )
    (comp (ref "C81")
      (value "10uF")
      (footprint "easyedapro:C0805")
      (description "容值:10uF;精度:±10%;额定电压:50V;材质(温度系数):X5R;")
      (fields
        (field (name "Manufacturer Part") "GRM21BR61H106KE43L")
        (field (name "Manufacturer") "muRata(村田)")
      )
      (libsource (lib "easyedapro") (part "GRM21BR61H106KE43L"))
    )
    (comp (ref "C82")
      (value "2.7nF")
      (footprint "easyedapro:C0603")
      (description "容值:2.7nF;精度:±5%;额定电压:50V;材质(温度系数):NP0;")
      (fields
        (field (name "Manufacturer Part") "CC0603JRNPO9BN272")
        (field (name "Manufacturer") "YAGEO(国巨)")
      )
      (libsource (lib "easyedapro") (part "CC0603JRNPO9BN272"))
    )
    (comp (ref "C83")
      (value "120pF")
      (fields
        (field (name "Manufacturer Part") "CC0603JRNPO0BN121")
        (field (name "Manufacturer") "YAGEO(国巨)")
      )
      (libsource (lib "easyedapro") (part "tcc0402cog121j500at"))
    )
    (comp (ref "C84")
      (value "680pF")
      (footprint "easyedapro:C0603")
      (description "容值:680pF;精度:±1%;额定电压:50V;材质(温度系数):NP0;")
      (fields
        (field (name "Manufacturer Part") "CC0603FRNPO9BN681")
        (field (name "Manufacturer") "YAGEO(国巨)")
      )
      (libsource (lib "easyedapro") (part "CC0603FRNPO9BN681"))
    )
    (comp (ref "C85")
      (value "56pF")
      (footprint "easyedapro:C0805")
      (description "容值:56pF;精度:±5%;额定电压:200V;材质(温度系数):NP0;")
      (fields
        (field (name "Manufacturer Part") "CC0805JRNPOABN560")
        (field (name "Manufacturer") "YAGEO(国巨)")
      )
      (libsource (lib "easyedapro") (part "CC0805JRNPOABN560"))
    )
    (comp (ref "C86")
      (value "470pF")
      (fields (field (name "Manufacturer Part") "0805B471K101CT") (field (name "Manufacturer") "Walsin(华新科)"))
      (libsource (lib "easyedapro") (part "tcc1206x7r471k102dts"))
    )
    (comp (ref "C87")
      (value "2.2nF")
      (fields
        (field (name "Manufacturer Part") "CL21C222JBFNNNE")
        (field (name "Manufacturer") "SAMSUNG(三星)")
      )
      (libsource (lib "easyedapro") (part "tcc1206x7r222k102dts"))
    )
    (comp (ref "C88")
      (value "3.9nF")
      (footprint "easyedapro:C0805")
      (description "容值:3.9nF;精度:±1%;额定电压:50V;材质(温度系数):NP0;")
      (fields
        (field (name "Manufacturer Part") "CC0805FKNPO9BN392")
        (field (name "Manufacturer") "YAGEO(国巨)")
      )
      (libsource (lib "easyedapro") (part "CC0805FKNPO9BN392"))
    )
    (comp (ref "CN2")
      (value "DB128V-5.08-6P-GN-S")
      (footprint "easyedapro:CONN-TH_6P-P5.08_DIBO_DB128V-5.08")
      (fields (field (name "Manufacturer") "DORABO(地博电气)"))
      (libsource (lib "easyedapro") (part "DB128V-5.08-6P-GN-S"))
    )
    (comp (ref "R39")
      (value "2kΩ")
      (fields
        (field (name "Manufacturer Part") "0805W8F2001T5E")
        (field (name "Manufacturer") "UNI-ROYAL(厚声)")
      )
      (libsource (lib "easyedapro") (part "0603waf2001t5e"))
    )
    (comp (ref "R40")
      (value "22kΩ")
      (fields (field (name "Manufacturer Part") "HPCR0805F22K0K9") (field (name "Manufacturer") "RESI(开步睿思）"))
      (libsource (lib "easyedapro") (part "0603waf2202t5e"))
    )
    (comp (ref "R41")
      (value "1.2kΩ")
      (footprint "easyedapro:R0805")
      (description "电阻类型:厚膜电阻;阻值:1.2kΩ;精度:±1%;功率:250mW;")
      (fields (field (name "Manufacturer Part") "RK73H2ATTD1201F") (field (name "Manufacturer") "KOA"))
      (libsource (lib "easyedapro") (part "RK73H2ATTD1201F"))
    )
    (comp (ref "R42")
      (value "4.7kΩ")
      (footprint "easyedapro:R1206")
      (description "阻值:4.7kΩ;精度:±5%;功率:250mW;温度系数:±100ppm/°C;电阻类型:厚膜电阻;")
      (fields
        (field (name "Manufacturer Part") "1206W4J0472T5E")
        (field (name "Manufacturer") "UNI-ROYAL(厚声)")
      )
      (libsource (lib "easyedapro") (part "1206W4J0472T5E"))
    )
    (comp (ref "R43")
      (value "27kΩ")
      (fields
        (field (name "Manufacturer Part") "0805W8F2702T5E")
        (field (name "Manufacturer") "UNI-ROYAL(厚声)")
      )
      (libsource (lib "easyedapro") (part "0603waf2702t5e"))
    )
    (comp (ref "R44")
      (value "0Ω")
      (footprint "easyedapro:R0603")
      (description "阻值:0Ω;精度:±1%;功率:100mW;电阻类型:厚膜电阻;")
      (fields
        (field (name "Manufacturer Part") "0603WAF0000T5E")
        (field (name "Manufacturer") "UNI-ROYAL(厚声)")
      )
      (libsource (lib "easyedapro") (part "0603WAF0000T5E"))
    )
    (comp (ref "R45")
      (value "2kΩ")
      (fields
        (field (name "Manufacturer Part") "0805W8F2001T5E")
        (field (name "Manufacturer") "UNI-ROYAL(厚声)")
      )
      (libsource (lib "easyedapro") (part "0603waf2001t5e"))
    )
    (comp (ref "R46")
      (value "22kΩ")
      (fields (field (name "Manufacturer Part") "HPCR0805F22K0K9") (field (name "Manufacturer") "RESI(开步睿思）"))
      (libsource (lib "easyedapro") (part "0603waf2202t5e"))
    )
    (comp (ref "R47")
      (value "750Ω")
      (footprint "easyedapro:R1206")
      (description "阻值:750Ω;精度:±1%;功率:250mW;温度系数:±100ppm/°C;电阻类型:厚膜电阻;")
      (fields
        (field (name "Manufacturer Part") "1206W4F7500T5E")
        (field (name "Manufacturer") "UNI-ROYAL(厚声)")
      )
      (libsource (lib "easyedapro") (part "1206W4F7500T5E"))
    )
    (comp (ref "R48")
      (value "1.2kΩ")
      (footprint "easyedapro:R0805")
      (description "电阻类型:厚膜电阻;阻值:1.2kΩ;精度:±1%;功率:250mW;")
      (fields (field (name "Manufacturer Part") "RK73H2ATTD1201F") (field (name "Manufacturer") "KOA"))
      (libsource (lib "easyedapro") (part "RK73H2ATTD1201F"))
    )
    (comp (ref "R49")
      (value "4.7kΩ")
      (footprint "easyedapro:R1206")
      (description "阻值:4.7kΩ;精度:±5%;功率:250mW;温度系数:±100ppm/°C;电阻类型:厚膜电阻;")
      (fields
        (field (name "Manufacturer Part") "1206W4J0472T5E")
        (field (name "Manufacturer") "UNI-ROYAL(厚声)")
      )
      (libsource (lib "easyedapro") (part "1206W4J0472T5E"))
    )
    (comp (ref "R50")
      (value "27kΩ")
      (fields
        (field (name "Manufacturer Part") "0805W8F2702T5E")
        (field (name "Manufacturer") "UNI-ROYAL(厚声)")
      )
      (libsource (lib "easyedapro") (part "0603waf2702t5e"))
    )
    (comp (ref "R51")
      (value "3.3kΩ")
      (fields
        (field (name "Manufacturer Part") "0805W8F3301T5E")
        (field (name "Manufacturer") "UNI-ROYAL(厚声)")
      )
      (libsource (lib "easyedapro") (part "0603waf3301t5e"))
    )
    (comp (ref "R52")
      (value "910Ω")
      (fields
        (field (name "Manufacturer Part") "0805W8F9100T5E")
        (field (name "Manufacturer") "UNI-ROYAL(厚声)")
      )
      (libsource (lib "easyedapro") (part "rc0603fr-07910rl"))
    )
    (comp (ref "R53")
      (value "0Ω")
      (footprint "easyedapro:R0603")
      (description "阻值:0Ω;精度:±1%;功率:100mW;电阻类型:厚膜电阻;")
      (fields
        (field (name "Manufacturer Part") "0603WAF0000T5E")
        (field (name "Manufacturer") "UNI-ROYAL(厚声)")
      )
      (libsource (lib "easyedapro") (part "0603WAF0000T5E"))
    )
    (comp (ref "R54")
      (value "20kΩ")
      (footprint "easyedapro:R0805")
      (description "电阻类型:厚膜电阻;阻值:20kΩ;精度:±1%;功率:125mW;")
      (fields
        (field (name "Manufacturer Part") "0805W8F2002T5E")
        (field (name "Manufacturer") "UNI-ROYAL(厚声)")
      )
      (libsource (lib "easyedapro") (part "0805W8F2002T5E"))
    )
    (comp (ref "R55")
      (value "2kΩ")
      (fields
        (field (name "Manufacturer Part") "0805W8F2001T5E")
        (field (name "Manufacturer") "UNI-ROYAL(厚声)")
      )
      (libsource (lib "easyedapro") (part "0603waf2001t5e"))
    )
    (comp (ref "R56")
      (value "20kΩ")
      (footprint "easyedapro:R0805")
      (description "电阻类型:厚膜电阻;阻值:20kΩ;精度:±1%;功率:125mW;")
      (fields
        (field (name "Manufacturer Part") "0805W8F2002T5E")
        (field (name "Manufacturer") "UNI-ROYAL(厚声)")
      )
      (libsource (lib "easyedapro") (part "0805W8F2002T5E"))
    )
    (comp (ref "R57")
      (value "6.2kΩ")
      (fields
        (field (name "Manufacturer Part") "0805W8F6201T5E")
        (field (name "Manufacturer") "UNI-ROYAL(厚声)")
      )
      (libsource (lib "easyedapro") (part "0603waf6201t5e"))
    )
    (comp (ref "R58")
      (value "820Ω")
      (fields
        (field (name "Manufacturer Part") "0805W8F8200T5E")
        (field (name "Manufacturer") "UNI-ROYAL(厚声)")
      )
      (libsource (lib "easyedapro") (part "0603waf8200t5e"))
    )
    (comp (ref "R59")
      (value "22kΩ")
      (fields (field (name "Manufacturer Part") "HPCR0805F22K0K9") (field (name "Manufacturer") "RESI(开步睿思）"))
      (libsource (lib "easyedapro") (part "0603waf2202t5e"))
    )
    (comp (ref "R60")
      (value "1.2kΩ")
      (footprint "easyedapro:R0805")
      (description "电阻类型:厚膜电阻;阻值:1.2kΩ;精度:±1%;功率:250mW;")
      (fields (field (name "Manufacturer Part") "RK73H2ATTD1201F") (field (name "Manufacturer") "KOA"))
      (libsource (lib "easyedapro") (part "RK73H2ATTD1201F"))
    )
    (comp (ref "R61")
      (value "4.7kΩ")
      (footprint "easyedapro:R1206")
      (description "阻值:4.7kΩ;精度:±5%;功率:250mW;温度系数:±100ppm/°C;电阻类型:厚膜电阻;")
      (fields
        (field (name "Manufacturer Part") "1206W4J0472T5E")
        (field (name "Manufacturer") "UNI-ROYAL(厚声)")
      )
      (libsource (lib "easyedapro") (part "1206W4J0472T5E"))
    )
    (comp (ref "R62")
      (value "27kΩ")
      (fields
        (field (name "Manufacturer Part") "0805W8F2702T5E")
        (field (name "Manufacturer") "UNI-ROYAL(厚声)")
      )
      (libsource (lib "easyedapro") (part "0603waf2702t5e"))
    )
    (comp (ref "R63")
      (value "0Ω")
      (footprint "easyedapro:R0603")
      (description "阻值:0Ω;精度:±1%;功率:100mW;电阻类型:厚膜电阻;")
      (fields
        (field (name "Manufacturer Part") "0603WAF0000T5E")
        (field (name "Manufacturer") "UNI-ROYAL(厚声)")
      )
      (libsource (lib "easyedapro") (part "0603WAF0000T5E"))
    )
    (comp (ref "R64")
      (value "750Ω")
      (footprint "easyedapro:R1206")
      (description "阻值:750Ω;精度:±1%;功率:250mW;温度系数:±100ppm/°C;电阻类型:厚膜电阻;")
      (fields
        (field (name "Manufacturer Part") "1206W4F7500T5E")
        (field (name "Manufacturer") "UNI-ROYAL(厚声)")
      )
      (libsource (lib "easyedapro") (part "1206W4F7500T5E"))
    )
    (comp (ref "R65")
      (value "3.3kΩ")
      (fields
        (field (name "Manufacturer Part") "0805W8F3301T5E")
        (field (name "Manufacturer") "UNI-ROYAL(厚声)")
      )
      (libsource (lib "easyedapro") (part "0603waf3301t5e"))
    )
    (comp (ref "R66")
      (value "910Ω")
      (fields
        (field (name "Manufacturer Part") "0805W8F9100T5E")
        (field (name "Manufacturer") "UNI-ROYAL(厚声)")
      )
      (libsource (lib "easyedapro") (part "rc0603fr-07910rl"))
    )
    (comp (ref "R67")
      (value "2kΩ")
      (fields
        (field (name "Manufacturer Part") "0805W8F2001T5E")
        (field (name "Manufacturer") "UNI-ROYAL(厚声)")
      )
      (libsource (lib "easyedapro") (part "0603waf2001t5e"))
    )
    (comp (ref "R68")
      (value "22kΩ")
      (fields (field (name "Manufacturer Part") "HPCR0805F22K0K9") (field (name "Manufacturer") "RESI(开步睿思）"))
      (libsource (lib "easyedapro") (part "0603waf2202t5e"))
    )
    (comp (ref "R69")
      (value "20kΩ")
      (footprint "easyedapro:R0805")
      (description "电阻类型:厚膜电阻;阻值:20kΩ;精度:±1%;功率:125mW;")
      (fields
        (field (name "Manufacturer Part") "0805W8F2002T5E")
        (field (name "Manufacturer") "UNI-ROYAL(厚声)")
      )
      (libsource (lib "easyedapro") (part "0805W8F2002T5E"))
    )
    (comp (ref "R70")
      (value "20kΩ")
      (footprint "easyedapro:R0805")
      (description "电阻类型:厚膜电阻;阻值:20kΩ;精度:±1%;功率:125mW;")
      (fields
        (field (name "Manufacturer Part") "0805W8F2002T5E")
        (field (name "Manufacturer") "UNI-ROYAL(厚声)")
      )
      (libsource (lib "easyedapro") (part "0805W8F2002T5E"))
    )
    (comp (ref "R71")
      (value "6.2kΩ")
      (fields
        (field (name "Manufacturer Part") "0805W8F6201T5E")
        (field (name "Manufacturer") "UNI-ROYAL(厚声)")
      )
      (libsource (lib "easyedapro") (part "0603waf6201t5e"))
    )
    (comp (ref "R72")
      (value "1.2kΩ")
      (footprint "easyedapro:R0805")
      (description "电阻类型:厚膜电阻;阻值:1.2kΩ;精度:±1%;功率:250mW;")
      (fields (field (name "Manufacturer Part") "RK73H2ATTD1201F") (field (name "Manufacturer") "KOA"))
      (libsource (lib "easyedapro") (part "RK73H2ATTD1201F"))
    )
    (comp (ref "R73")
      (value "4.7kΩ")
      (footprint "easyedapro:R1206")
      (description "阻值:4.7kΩ;精度:±5%;功率:250mW;温度系数:±100ppm/°C;电阻类型:厚膜电阻;")
      (fields
        (field (name "Manufacturer Part") "1206W4J0472T5E")
        (field (name "Manufacturer") "UNI-ROYAL(厚声)")
      )
      (libsource (lib "easyedapro") (part "1206W4J0472T5E"))
    )
    (comp (ref "R74")
      (value "27kΩ")
      (fields
        (field (name "Manufacturer Part") "0805W8F2702T5E")
        (field (name "Manufacturer") "UNI-ROYAL(厚声)")
      )
      (libsource (lib "easyedapro") (part "0603waf2702t5e"))
    )
    (comp (ref "R75")
      (value "820Ω")
      (fields
        (field (name "Manufacturer Part") "0805W8F8200T5E")
        (field (name "Manufacturer") "UNI-ROYAL(厚声)")
      )
      (libsource (lib "easyedapro") (part "0603waf8200t5e"))
    )
    (comp (ref "R76")
      (value "0Ω")
      (footprint "easyedapro:R0603")
      (description "阻值:0Ω;精度:±1%;功率:100mW;电阻类型:厚膜电阻;")
      (fields
        (field (name "Manufacturer Part") "0603WAF0000T5E")
        (field (name "Manufacturer") "UNI-ROYAL(厚声)")
      )
      (libsource (lib "easyedapro") (part "0603WAF0000T5E"))
    )
    (comp (ref "U10")
      (value "AD2S1210BSTZ")
      (footprint "easyedapro:LQFP-48_L7.0-W7.0-P0.50-LS9.0-BL")
      (description "接口:-;差分输入:-;通道数:-;积分非线性:-;采样率:-;分辨率:-;电源电压:4.75V~5.25V;工作温度:-;")
      (fields (field (name "Manufacturer") "ADI(亚德诺)/LINEAR(凌特)"))
      (libsource (lib "easyedapro") (part "AD2S1210BSTZ"))
    )
    (comp (ref "U13")
      (value "TX49S8.192M2LDBE2S")
      (footprint "easyedapro:HC-49S_L11.5-W5.0-P4.88")
      (description "频率：8.192MHz 频率公差：±20ppm 频率稳定度：±30ppm 负载电容：20F 工作温度：-20°C~+70°C")
      (fields (field (name "Manufacturer") "TAE(雅晶鑫)"))
      (libsource (lib "easyedapro") (part "TX49S8.192M2LDBE2S"))
    )
    (comp (ref "U24")
      (value "{ManufacturerPart!}")
      (footprint "easyedapro:SOP-8_L4.9-W3.9-P1.27-LS6.0-BL-EP2.1")
      (description "放大器组数:2;带宽(-3db):69MHz;输入偏置电流(Ib):200pA;增益带宽积(GBP):35MHz;压摆率(SR):53V/us;")
      (fields (field (name "Manufacturer Part") "AD8397ARDZ-REEL7") (field (name "Manufacturer") "ADI(亚德诺)"))
      (libsource (lib "easyedapro") (part "AD8397ARDZ-REEL7"))
    )
    (comp (ref "U25")
      (value "{ManufacturerPart!}")
      (footprint "easyedapro:TSSOP-14_L5.0-W4.5-P0.65-LS6.4-BL")
      (description "通用-放大器-4-电路-满摆幅-14-TSSOP")
      (fields
        (field (name "Manufacturer Part") "AD8694ARUZ")
        (field (name "Manufacturer") "ADI(亚德诺)/LINEAR(凌特)")
      )
      (libsource (lib "easyedapro") (part "AD8694ARUZ"))
    )
    (comp (ref "U26")
      (value "{ManufacturerPart!}")
      (footprint "easyedapro:TSSOP-14_L5.0-W4.5-P0.65-LS6.4-BL")
      (description "通用-放大器-4-电路-满摆幅-14-TSSOP")
      (fields
        (field (name "Manufacturer Part") "AD8694ARUZ")
        (field (name "Manufacturer") "ADI(亚德诺)/LINEAR(凌特)")
      )
      (libsource (lib "easyedapro") (part "AD8694ARUZ"))
    )
    (comp (ref "U27")
      (value "AD8692ARZ-REEL7")
      (footprint "easyedapro:SOIC-8_L4.9-W3.9-P1.27-LS6.0-BL")
      (description "放大器组数:2;")
      (fields (field (name "Manufacturer") "ADI(亚德诺)/LINEAR(凌特)"))
      (libsource (lib "easyedapro") (part "AD8692ARZ-REEL7"))
    )
  )
  (nets
    (net (code "1") (name "+3.3V") (class "Default")
      (node (ref "C10") (pin "2") (pinfunction "2_2") (pintype "input"))
      (node (ref "C4") (pin "2") (pinfunction "2_2") (pintype "input"))
      (node (ref "C5") (pin "2") (pinfunction "2_2") (pintype "input"))
      (node (ref "C6") (pin "2") (pinfunction "2_2") (pintype "input"))
      (node (ref "C7") (pin "2") (pinfunction "2_2") (pintype "input"))
      (node (ref "C76") (pin "2") (pinfunction "2_2") (pintype "unspecified"))
      (node (ref "C8") (pin "2") (pinfunction "2_2") (pintype "input"))
      (node (ref "C9") (pin "2") (pinfunction "2_2") (pintype "input"))
      (node (ref "CN4") (pin "4") (pinfunction "4_4") (pintype "unspecified"))
      (node (ref "H1") (pin "1") (pinfunction "1_1") (pintype "input"))
      (node (ref "L1") (pin "1") (pinfunction "1_1") (pintype "unspecified"))
      (node (ref "R38") (pin "2") (pinfunction "2_2") (pintype "input"))
      (node (ref "U1") (pin "100") (pinfunction "VDD_100") (pintype "input"))
      (node (ref "U1") (pin "24") (pinfunction "VDD_24") (pintype "input"))
      (node (ref "U1") (pin "49") (pinfunction "VDD_49") (pintype "input"))
      (node (ref "U1") (pin "6") (pinfunction "VBAT_6") (pintype "input"))
      (node (ref "U1") (pin "64") (pinfunction "VDD_64") (pintype "input"))
      (node (ref "U1") (pin "75") (pinfunction "VDD_75") (pintype "input"))
      (node (ref "U10") (pin "18") (pinfunction "VDRIVE_18") (pintype "input"))
    )
    (net (code "2") (name "+5V") (class "Default")
      (node (ref "C53") (pin "2") (pinfunction "2_2") (pintype "unspecified"))
      (node (ref "C73") (pin "2") (pinfunction "2_2") (pintype "input"))
      (node (ref "C77") (pin "2") (pinfunction "2_2") (pintype "input"))
      (node (ref "C79") (pin "2") (pinfunction "2_2") (pintype "input"))
      (node (ref "CN4") (pin "2") (pinfunction "2_2") (pintype "unspecified"))
      (node (ref "U10") (pin "43") (pinfunction "AVDD_43") (pintype "input"))
      (node (ref "U25") (pin "4") (pinfunction "V+_4") (pintype "input"))
      (node (ref "U26") (pin "4") (pinfunction "V+_4") (pintype "input"))
      (node (ref "U27") (pin "8") (pinfunction "V+_8") (pintype "input"))
      (node (ref "U9") (pin "3") (pinfunction "VCC_3") (pintype "input"))
    )
    (net (code "3") (name "+12V") (class "Default")
      (node (ref "C81") (pin "2") (pinfunction "2_2") (pintype "input"))
      (node (ref "CN4") (pin "1") (pinfunction "1_1") (pintype "unspecified"))
      (node (ref "U24") (pin "8") (pinfunction "VDD_8") (pintype "input"))
    )
    (net (code "4") (name "A0") (class "Default")
      (node (ref "U1") (pin "91") (pinfunction "PB4_91") (pintype "input"))
      (node (ref "U10") (pin "37") (pinfunction "A0_37") (pintype "input"))
    )
    (net (code "5") (name "A1") (class "Default")
      (node (ref "U1") (pin "92") (pinfunction "PB5_92") (pintype "input"))
      (node (ref "U10") (pin "36") (pinfunction "A1_36") (pintype "input"))
    )
    (net (code "6") (name "AGND") (class "Default")
      (node (ref "C1") (pin "2") (pinfunction "2_2") (pintype "input"))
      (node (ref "C10") (pin "1") (pinfunction "1_1") (pintype "input"))
      (node (ref "C11") (pin "1") (pinfunction "1_1") (pintype "input"))
      (node (ref "C12") (pin "1") (pinfunction "1_1") (pintype "unspecified"))
      (node (ref "C2") (pin "1") (pinfunction "1_1") (pintype "input"))
      (node (ref "C3") (pin "2") (pinfunction "2_2") (pintype "input"))
      (node (ref "C4") (pin "1") (pinfunction "1_1") (pintype "input"))
      (node (ref "C5") (pin "1") (pinfunction "1_1") (pintype "input"))
      (node (ref "C53") (pin "1") (pinfunction "1_1") (pintype "unspecified"))
      (node (ref "C55") (pin "1") (pinfunction "1_1") (pintype "input"))
      (node (ref "C56") (pin "1") (pinfunction "1_1") (pintype "input"))
      (node (ref "C57") (pin "1") (pinfunction "1_1") (pintype "unspecified"))
      (node (ref "C59") (pin "1") (pinfunction "1_1") (pintype "unspecified"))
      (node (ref "C6") (pin "1") (pinfunction "1_1") (pintype "input"))
      (node (ref "C60") (pin "2") (pinfunction "2_2") (pintype "input"))
      (node (ref "C61") (pin "2") (pinfunction "2_2") (pintype "input"))
      (node (ref "C65") (pin "1") (pinfunction "1_1") (pintype "unspecified"))
      (node (ref "C68") (pin "1") (pinfunction "1_1") (pintype "input"))
      (node (ref "C7") (pin "1") (pinfunction "1_1") (pintype "input"))
      (node (ref "C71") (pin "1") (pinfunction "1_1") (pintype "unspecified"))
      (node (ref "C72") (pin "2") (pinfunction "2_2") (pintype "input"))
      (node (ref "C73") (pin "1") (pinfunction "1_1") (pintype "input"))
      (node (ref "C74") (pin "1") (pinfunction "1_1") (pintype "unspecified"))
      (node (ref "C75") (pin "1") (pinfunction "1_1") (pintype "unspecified"))
      (node (ref "C76") (pin "1") (pinfunction "1_1") (pintype "unspecified"))
      (node (ref "C77") (pin "1") (pinfunction "1_1") (pintype "input"))
      (node (ref "C78") (pin "1") (pinfunction "1_1") (pintype "unspecified"))
      (node (ref "C79") (pin "1") (pinfunction "1_1") (pintype "input"))
      (node (ref "C8") (pin "1") (pinfunction "1_1") (pintype "input"))
      (node (ref "C80") (pin "1") (pinfunction "1_1") (pintype "unspecified"))
      (node (ref "C81") (pin "1") (pinfunction "1_1") (pintype "input"))
      (node (ref "C86") (pin "1") (pinfunction "1_1") (pintype "input"))
      (node (ref "C87") (pin "2") (pinfunction "2_2") (pintype "input"))
      (node (ref "C88") (pin "1") (pinfunction "1_1") (pintype "unspecified"))
      (node (ref "C9") (pin "1") (pinfunction "1_1") (pintype "input"))
      (node (ref "CN4") (pin "5") (pinfunction "5_5") (pintype "unspecified"))
      (node (ref "H1") (pin "4") (pinfunction "4_4") (pintype "input"))
      (node (ref "H2") (pin "3") (pinfunction "3_3") (pintype "input"))
      (node (ref "R1") (pin "2") (pinfunction "2_2") (pintype "input"))
      (node (ref "R47") (pin "1") (pinfunction "1_1") (pintype "input"))
      (node (ref "R51") (pin "1") (pinfunction "1_1") (pintype "input"))
      (node (ref "R64") (pin "1") (pinfunction "1_1") (pintype "input"))
      (node (ref "R65") (pin "1") (pinfunction "1_1") (pintype "input"))
      (node (ref "SW1") (pin "1") (pinfunction "1_1") (pintype "input"))
      (node (ref "U1") (pin "23") (pinfunction "VSS_23") (pintype "input"))
      (node (ref "U1") (pin "35") (pinfunction "VSSA_35") (pintype "input"))
      (node (ref "U1") (pin "48") (pinfunction "VSS_48") (pintype "input"))
      (node (ref "U1") (pin "63") (pinfunction "VSS_63") (pintype "input"))
      (node (ref "U1") (pin "74") (pinfunction "VSS_74") (pintype "input"))
      (node (ref "U1") (pin "99") (pinfunction "VSS_99") (pintype "input"))
      (node (ref "U10") (pin "19") (pinfunction "DGND_19") (pintype "input"))
      (node (ref "U10") (pin "40") (pinfunction "AGND_40") (pintype "input"))
      (node (ref "U10") (pin "5") (pinfunction "DGND_5") (pintype "input"))
      (node (ref "U24") (pin "4") (pinfunction "VSS_4") (pintype "input"))
      (node (ref "U24") (pin "9") (pinfunction "EP_9") (pintype "input"))
      (node (ref "U25") (pin "11") (pinfunction "V-_11") (pintype "input"))
      (node (ref "U26") (pin "11") (pinfunction "V-_11") (pintype "input"))
      (node (ref "U27") (pin "4") (pinfunction "V-_4") (pintype "input"))
      (node (ref "U9") (pin "2") (pinfunction "GND_2") (pintype "input"))
      (node (ref "U9") (pin "8") (pinfunction "S_8") (pintype "input"))
    )
    (net (code "7") (name "CANH") (class "Default")
      (node (ref "H3") (pin "1") (pinfunction "1_1") (pintype "input"))
      (node (ref "R37") (pin "2") (pinfunction "2_2") (pintype "unspecified"))
      (node (ref "U9") (pin "7") (pinfunction "CANH_7") (pintype "input"))
    )
    (net (code "8") (name "CANL") (class "Default")
      (node (ref "H3") (pin "2") (pinfunction "2_2") (pintype "input"))
      (node (ref "R37") (pin "1") (pinfunction "1_1") (pintype "unspecified"))
      (node (ref "U9") (pin "6") (pinfunction "CANL_6") (pintype "input"))
    )
    (net (code "9") (name "CAN_RX") (class "Default")
      (node (ref "U1") (pin "72") (pinfunction "PA11_72") (pintype "input"))
      (node (ref "U9") (pin "4") (pinfunction "RXD_4") (pintype "input"))
    )
    (net (code "10") (name "CAN_TX") (class "Default")
      (node (ref "U1") (pin "73") (pinfunction "PA12_73") (pintype "input"))
      (node (ref "U9") (pin "1") (pinfunction "TXD_1") (pintype "input"))
    )
    (net (code "11") (name "COS") (class "Default")
      (node (ref "C58") (pin "1") (pinfunction "1_1") (pintype "unspecified"))
      (node (ref "R39") (pin "2") (pinfunction "2_2") (pintype "input"))
      (node (ref "U10") (pin "45") (pinfunction "COS_45") (pintype "input"))
      (node (ref "U26") (pin "14") (pinfunction "OUT_D_14") (pintype "output"))
    )
    (net (code "12") (name "COSLO") (class "Default")
      (node (ref "C63") (pin "1") (pinfunction "1_1") (pintype "unspecified"))
      (node (ref "R45") (pin "2") (pinfunction "2_2") (pintype "input"))
      (node (ref "U10") (pin "44") (pinfunction "COSLO_44") (pintype "input"))
      (node (ref "U26") (pin "8") (pinfunction "OUT_C_8") (pintype "output"))
    )
    (net (code "13") (name "CS#") (class "Default")
      (node (ref "U1") (pin "19") (pinfunction "PF2_19") (pintype "input"))
      (node (ref "U10") (pin "2") (pinfunction "CS#_2") (pintype "input"))
    )
    (net (code "14") (name "D+5V") (class "Default")
      (node (ref "C75") (pin "2") (pinfunction "2_2") (pintype "unspecified"))
      (node (ref "CN4") (pin "3") (pinfunction "3_3") (pintype "unspecified"))
      (node (ref "U10") (pin "6") (pinfunction "DVDD_6") (pintype "input"))
    )
    (net (code "15") (name "DB13") (class "Default")
      (node (ref "U1") (pin "1") (pinfunction "PE2_1") (pintype "input"))
      (node (ref "U10") (pin "13") (pinfunction "DB13/SCLK_13") (pintype "input"))
    )
    (net (code "16") (name "DB14") (class "Default")
      (node (ref "U1") (pin "5") (pinfunction "PE6_5") (pintype "input"))
      (node (ref "U10") (pin "12") (pinfunction "DB14/SDI_12") (pintype "input"))
    )
    (net (code "17") (name "DB15") (class "Default")
      (node (ref "U1") (pin "4") (pinfunction "PE5_4") (pintype "input"))
      (node (ref "U10") (pin "11") (pinfunction "DB15/SDO_11") (pintype "input"))
    )
    (net (code "18") (name "DIR") (class "Default")
      (node (ref "U1") (pin "7") (pinfunction "PC13_7") (pintype "input"))
      (node (ref "U10") (pin "32") (pinfunction "DIR_32") (pintype "input"))
    )
    (net (code "19") (name "DOS") (class "Default")
      (node (ref "U1") (pin "97") (pinfunction "PE0_97") (pintype "input"))
      (node (ref "U10") (pin "35") (pinfunction "DOS_35") (pintype "input"))
    )
    (net (code "20") (name "EXC") (class "Default")
      (node (ref "R70") (pin "1") (pinfunction "1_1") (pintype "input"))
      (node (ref "U10") (pin "38") (pinfunction "EXC_38") (pintype "input"))
    )
    (net (code "21") (name "EXC#") (class "Default")
      (node (ref "R56") (pin "1") (pinfunction "1_1") (pintype "input"))
      (node (ref "U10") (pin "39") (pinfunction "EXC#_39") (pintype "input"))
    )
    (net (code "22") (name "LOT") (class "Default")
      (node (ref "U1") (pin "98") (pinfunction "PE1_98") (pintype "input"))
      (node (ref "U10") (pin "34") (pinfunction "LOT_34") (pintype "input"))
    )
    (net (code "23") (name "NRST") (class "Default")
      (node (ref "C2") (pin "2") (pinfunction "2_2") (pintype "input"))
      (node (ref "SW1") (pin "2") (pinfunction "2_2") (pintype "input"))
      (node (ref "U1") (pin "14") (pinfunction "PG10-NRST_14") (pintype "input"))
    )
    (net (code "24") (name "Net-(C59-Pad2)") (class "Default")
      (node (ref "C59") (pin "2") (pinfunction "2_2") (pintype "unspecified"))
      (node (ref "R39") (pin "1") (pinfunction "1_1") (pintype "input"))
      (node (ref "R41") (pin "2") (pinfunction "2_2") (pintype "input"))
      (node (ref "R42") (pin "1") (pinfunction "1_1") (pintype "input"))
    )
    (net (code "25") (name "Net-(C65-Pad2)") (class "Default")
      (node (ref "C65") (pin "2") (pinfunction "2_2") (pintype "unspecified"))
      (node (ref "R45") (pin "1") (pinfunction "1_1") (pintype "input"))
      (node (ref "R48") (pin "2") (pinfunction "2_2") (pintype "input"))
      (node (ref "R49") (pin "1") (pinfunction "1_1") (pintype "input"))
    )
    (net (code "26") (name "Net-(C68-Pad2)") (class "Default")
      (node (ref "C68") (pin "2") (pinfunction "2_2") (pintype "input"))
      (node (ref "R54") (pin "1") (pinfunction "1_1") (pintype "input"))
      (node (ref "R56") (pin "2") (pinfunction "2_2") (pintype "input"))
      (node (ref "R57") (pin "1") (pinfunction "1_1") (pintype "input"))
    )
    (net (code "27") (name "Net-(C78-Pad2)") (class "Default")
      (node (ref "C78") (pin "2") (pinfunction "2_2") (pintype "unspecified"))
      (node (ref "R55") (pin "1") (pinfunction "1_1") (pintype "input"))
      (node (ref "R60") (pin "2") (pinfunction "2_2") (pintype "input"))
      (node (ref "R61") (pin "1") (pinfunction "1_1") (pintype "input"))
    )
    (net (code "28") (name "Net-(C86-Pad2)") (class "Default")
      (node (ref "C86") (pin "2") (pinfunction "2_2") (pintype "input"))
      (node (ref "R69") (pin "1") (pinfunction "1_1") (pintype "input"))
      (node (ref "R70") (pin "2") (pinfunction "2_2") (pintype "input"))
      (node (ref "R71") (pin "1") (pinfunction "1_1") (pintype "input"))
    )
    (net (code "29") (name "Net-(C88-Pad2)") (class "Default")
      (node (ref "C88") (pin "2") (pinfunction "2_2") (pintype "unspecified"))
      (node (ref "R67") (pin "1") (pinfunction "1_1") (pintype "input"))
      (node (ref "R72") (pin "2") (pinfunction "2_2") (pintype "input"))
      (node (ref "R73") (pin "1") (pinfunction "1_1") (pintype "input"))
    )
    (net (code "30") (name "Net-(CN2-Pad1)") (class "Default")
      (node (ref "CN2") (pin "1") (pinfunction "1_1") (pintype "unspecified"))
      (node (ref "R44") (pin "2") (pinfunction "2_2") (pintype "input"))
    )
    (net (code "31") (name "Net-(CN2-Pad2)") (class "Default")
      (node (ref "CN2") (pin "2") (pinfunction "2_2") (pintype "unspecified"))
      (node (ref "R53") (pin "2") (pinfunction "2_2") (pintype "input"))
    )
    (net (code "32") (name "Net-(CN2-Pad3)") (class "Default")
      (node (ref "CN2") (pin "3") (pinfunction "3_3") (pintype "unspecified"))
      (node (ref "R63") (pin "2") (pinfunction "2_2") (pintype "input"))
    )
    (net (code "33") (name "Net-(CN2-Pad4)") (class "Default")
      (node (ref "CN2") (pin "4") (pinfunction "4_4") (pintype "unspecified"))
      (node (ref "R76") (pin "2") (pinfunction "2_2") (pintype "input"))
    )
    (net (code "34") (name "Net-(R43-Pad1)") (class "Default")
      (node (ref "R43") (pin "1") (pinfunction "1_1") (pintype "input"))
      (node (ref "R44") (pin "1") (pinfunction "1_1") (pintype "input"))
    )
    (net (code "35") (name "Net-(R50-Pad1)") (class "Default")
      (node (ref "R50") (pin "1") (pinfunction "1_1") (pintype "input"))
      (node (ref "R53") (pin "1") (pinfunction "1_1") (pintype "input"))
    )
    (net (code "36") (name "Net-(R62-Pad1)") (class "Default")
      (node (ref "R62") (pin "1") (pinfunction "1_1") (pintype "input"))
      (node (ref "R63") (pin "1") (pinfunction "1_1") (pintype "input"))
    )
    (net (code "37") (name "Net-(R74-Pad1)") (class "Default")
      (node (ref "R74") (pin "1") (pinfunction "1_1") (pintype "input"))
      (node (ref "R76") (pin "1") (pinfunction "1_1") (pintype "input"))
    )
    (net (code "38") (name "Net-(U1-PB8-BOOT0)") (class "Default")
      (node (ref "R1") (pin "1") (pinfunction "1_1") (pintype "input"))
      (node (ref "U1") (pin "95") (pinfunction "PB8-BOOT0_95") (pintype "input"))
    )
    (net (code "39") (name "Net-(U1-VDDA)") (class "Default")
      (node (ref "C11") (pin "2") (pinfunction "2_2") (pintype "input"))
      (node (ref "C12") (pin "2") (pinfunction "2_2") (pintype "unspecified"))
      (node (ref "L1") (pin "2") (pinfunction "2_2") (pintype "unspecified"))
      (node (ref "U1") (pin "36") (pinfunction "VREF+_36") (pintype "input"))
      (node (ref "U1") (pin "37") (pinfunction "VDDA_37") (pintype "input"))
    )
    (net (code "40") (name "Net-(U9-VREF)") (class "Default")
      (node (ref "R38") (pin "1") (pinfunction "1_1") (pintype "input"))
      (node (ref "U9") (pin "5") (pinfunction "VREF_5") (pintype "input"))
    )
    (net (code "41") (name "Net-(U10-CLKIN)") (class "Default")
      (node (ref "C60") (pin "1") (pinfunction "1_1") (pintype "input"))
      (node (ref "U10") (pin "7") (pinfunction "CLKIN_7") (pintype "input"))
      (node (ref "U13") (pin "1") (pinfunction "OSC1_1") (pintype "input"))
    )
    (net (code "42") (name "Net-(U10-REFBYP)") (class "Default")
      (node (ref "C55") (pin "2") (pinfunction "2_2") (pintype "input"))
      (node (ref "C56") (pin "2") (pinfunction "2_2") (pintype "input"))
      (node (ref "U10") (pin "46") (pinfunction "REFBYP_46") (pintype "input"))
    )
    (net (code "43") (name "Net-(U10-XTALOUT)") (class "Default")
      (node (ref "C61") (pin "1") (pinfunction "1_1") (pintype "input"))
      (node (ref "U10") (pin "8") (pinfunction "XTALOUT_8") (pintype "input"))
      (node (ref "U13") (pin "2") (pinfunction "OSC2_2") (pintype "input"))
    )
    (net (code "44") (name "Net-(U24A-VINA+)") (class "Default")
      (node (ref "C72") (pin "1") (pinfunction "1_1") (pintype "input"))
      (node (ref "R58") (pin "2") (pinfunction "2_2") (pintype "input"))
      (node (ref "U24") (pin "3") (pinfunction "VINA+_3") (pintype "input"))
    )
    (net (code "45") (name "Net-(U24A-VINA-)") (class "Default")
      (node (ref "C64") (pin "2") (pinfunction "2_2") (pintype "unspecified"))
      (node (ref "R47") (pin "2") (pinfunction "2_2") (pintype "input"))
      (node (ref "R51") (pin "2") (pinfunction "2_2") (pintype "input"))
      (node (ref "R52") (pin "1") (pinfunction "1_1") (pintype "input"))
      (node (ref "U24") (pin "2") (pinfunction "VINA-_2") (pintype "input"))
    )
    (net (code "46") (name "Net-(U24A-VOUTA)") (class "Default")
      (node (ref "C64") (pin "1") (pinfunction "1_1") (pintype "unspecified"))
      (node (ref "CN2") (pin "5") (pinfunction "5_5") (pintype "unspecified"))
      (node (ref "R52") (pin "2") (pinfunction "2_2") (pintype "input"))
      (node (ref "U24") (pin "1") (pinfunction "VOUTA_1") (pintype "output"))
    )
    (net (code "47") (name "Net-(U24B-VINB+)") (class "Default")
      (node (ref "C87") (pin "1") (pinfunction "1_1") (pintype "input"))
      (node (ref "R75") (pin "2") (pinfunction "2_2") (pintype "input"))
      (node (ref "U24") (pin "5") (pinfunction "VINB+_5") (pintype "input"))
    )
    (net (code "48") (name "Net-(U24B-VINB-)") (class "Default")
      (node (ref "C82") (pin "2") (pinfunction "2_2") (pintype "unspecified"))
      (node (ref "R64") (pin "2") (pinfunction "2_2") (pintype "input"))
      (node (ref "R65") (pin "2") (pinfunction "2_2") (pintype "input"))
      (node (ref "R66") (pin "1") (pinfunction "1_1") (pintype "input"))
      (node (ref "U24") (pin "6") (pinfunction "VINB-_6") (pintype "input"))
    )
    (net (code "49") (name "Net-(U24B-VOUTB)") (class "Default")
      (node (ref "C82") (pin "1") (pinfunction "1_1") (pintype "unspecified"))
      (node (ref "CN2") (pin "6") (pinfunction "6_6") (pintype "unspecified"))
      (node (ref "R66") (pin "2") (pinfunction "2_2") (pintype "input"))
      (node (ref "U24") (pin "7") (pinfunction "VOUTB_7") (pintype "output"))
    )
    (net (code "50") (name "Net-(U25A-OUT_A)") (class "Default")
      (node (ref "C67") (pin "2") (pinfunction "2_2") (pintype "input"))
      (node (ref "R59") (pin "2") (pinfunction "2_2") (pintype "input"))
      (node (ref "R61") (pin "2") (pinfunction "2_2") (pintype "input"))
      (node (ref "U25") (pin "1") (pinfunction "OUT_A_1") (pintype "output"))
    )
    (net (code "51") (name "Net-(U25A-–IN_A)") (class "Default")
      (node (ref "C67") (pin "1") (pinfunction "1_1") (pintype "input"))
      (node (ref "R59") (pin "1") (pinfunction "1_1") (pintype "input"))
      (node (ref "R62") (pin "2") (pinfunction "2_2") (pintype "input"))
      (node (ref "U25") (pin "2") (pinfunction "–IN_A_2") (pintype "input"))
    )
    (net (code "52") (name "Net-(U25B-OUT_B)") (class "Default")
      (node (ref "C83") (pin "2") (pinfunction "2_2") (pintype "input"))
      (node (ref "R68") (pin "2") (pinfunction "2_2") (pintype "input"))
      (node (ref "R73") (pin "2") (pinfunction "2_2") (pintype "input"))
      (node (ref "U25") (pin "7") (pinfunction "OUT_B_7") (pintype "output"))
    )
    (net (code "53") (name "Net-(U25B-–IN_B)") (class "Default")
      (node (ref "C83") (pin "1") (pinfunction "1_1") (pintype "input"))
      (node (ref "R68") (pin "1") (pinfunction "1_1") (pintype "input"))
      (node (ref "R74") (pin "2") (pinfunction "2_2") (pintype "input"))
      (node (ref "U25") (pin "6") (pinfunction "–IN_B_6") (pintype "input"))
    )
    (net (code "54") (name "Net-(U25C-OUT_C)") (class "Default")
      (node (ref "C54") (pin "2") (pinfunction "2_2") (pintype "input"))
      (node (ref "R40") (pin "2") (pinfunction "2_2") (pintype "input"))
      (node (ref "R42") (pin "2") (pinfunction "2_2") (pintype "input"))
      (node (ref "U25") (pin "8") (pinfunction "OUT_C_8") (pintype "output"))
    )
    (net (code "55") (name "Net-(U25C-–IN_C)") (class "Default")
      (node (ref "C54") (pin "1") (pinfunction "1_1") (pintype "input"))
      (node (ref "R40") (pin "1") (pinfunction "1_1") (pintype "input"))
      (node (ref "R43") (pin "2") (pinfunction "2_2") (pintype "input"))
      (node (ref "U25") (pin "9") (pinfunction "–IN_C_9") (pintype "input"))
    )
    (net (code "56") (name "Net-(U25D-OUT_D)") (class "Default")
      (node (ref "C62") (pin "2") (pinfunction "2_2") (pintype "input"))
      (node (ref "R46") (pin "2") (pinfunction "2_2") (pintype "input"))
      (node (ref "R49") (pin "2") (pinfunction "2_2") (pintype "input"))
      (node (ref "U25") (pin "14") (pinfunction "OUT_D_14") (pintype "output"))
    )
    (net (code "57") (name "Net-(U25D-–IN_D)") (class "Default")
      (node (ref "C62") (pin "1") (pinfunction "1_1") (pintype "input"))
      (node (ref "R46") (pin "1") (pinfunction "1_1") (pintype "input"))
      (node (ref "R50") (pin "2") (pinfunction "2_2") (pintype "input"))
      (node (ref "U25") (pin "13") (pinfunction "–IN_D_13") (pintype "input"))
    )
    (net (code "58") (name "Net-(U26A-–IN_A)") (class "Default")
      (node (ref "C84") (pin "2") (pinfunction "2_2") (pintype "unspecified"))
      (node (ref "R72") (pin "1") (pinfunction "1_1") (pintype "input"))
      (node (ref "U26") (pin "2") (pinfunction "–IN_A_2") (pintype "input"))
    )
    (net (code "59") (name "Net-(U26B-–IN_B)") (class "Default")
      (node (ref "C69") (pin "2") (pinfunction "2_2") (pintype "unspecified"))
      (node (ref "R60") (pin "1") (pinfunction "1_1") (pintype "input"))
      (node (ref "U26") (pin "6") (pinfunction "–IN_B_6") (pintype "input"))
    )
    (net (code "60") (name "Net-(U26C-–IN_C)") (class "Default")
      (node (ref "C63") (pin "2") (pinfunction "2_2") (pintype "unspecified"))
      (node (ref "R48") (pin "1") (pinfunction "1_1") (pintype "input"))
      (node (ref "U26") (pin "9") (pinfunction "–IN_C_9") (pintype "input"))
    )
    (net (code "61") (name "Net-(U26D-–IN_D)") (class "Default")
      (node (ref "C58") (pin "2") (pinfunction "2_2") (pintype "unspecified"))
      (node (ref "R41") (pin "1") (pinfunction "1_1") (pintype "input"))
      (node (ref "U26") (pin "13") (pinfunction "–IN_D_13") (pintype "input"))
    )
    (net (code "62") (name "Net-(U27A--IN_A)") (class "Default")
      (node (ref "C66") (pin "1") (pinfunction "1_1") (pintype "unspecified"))
      (node (ref "R57") (pin "2") (pinfunction "2_2") (pintype "input"))
      (node (ref "U27") (pin "2") (pinfunction "-IN_A_2") (pintype "input"))
    )
    (net (code "63") (name "Net-(U27A-OUT_A)") (class "Default")
      (node (ref "C66") (pin "2") (pinfunction "2_2") (pintype "unspecified"))
      (node (ref "R54") (pin "2") (pinfunction "2_2") (pintype "input"))
      (node (ref "R58") (pin "1") (pinfunction "1_1") (pintype "input"))
      (node (ref "U27") (pin "1") (pinfunction "OUT_A_1") (pintype "output"))
    )
    (net (code "64") (name "Net-(U27B--IN_B)") (class "Default")
      (node (ref "C85") (pin "1") (pinfunction "1_1") (pintype "unspecified"))
      (node (ref "R71") (pin "2") (pinfunction "2_2") (pintype "input"))
      (node (ref "U27") (pin "6") (pinfunction "-IN_B_6") (pintype "input"))
    )
    (net (code "65") (name "Net-(U27B-OUT_B)") (class "Default")
      (node (ref "C85") (pin "2") (pinfunction "2_2") (pintype "unspecified"))
      (node (ref "R69") (pin "2") (pinfunction "2_2") (pintype "input"))
      (node (ref "R75") (pin "1") (pinfunction "1_1") (pintype "input"))
      (node (ref "U27") (pin "7") (pinfunction "OUT_B_7") (pintype "output"))
    )
    (net (code "66") (name "OSC_IN") (class "Default")
      (node (ref "C1") (pin "1") (pinfunction "1_1") (pintype "input"))
      (node (ref "U1") (pin "12") (pinfunction "PF0-OSC_IN_12") (pintype "input"))
      (node (ref "X1") (pin "2") (pinfunction "OSC2_2") (pintype "input"))
    )
    (net (code "67") (name "OSC_OUT") (class "Default")
      (node (ref "C3") (pin "1") (pinfunction "1_1") (pintype "input"))
      (node (ref "U1") (pin "13") (pinfunction "PF1-OSC_OUT_13") (pintype "input"))
      (node (ref "X1") (pin "1") (pinfunction "OSC1_1") (pintype "input"))
    )
    (net (code "68") (name "RD#") (class "Default")
      (node (ref "U1") (pin "18") (pinfunction "PC3_18") (pintype "input"))
      (node (ref "U10") (pin "3") (pinfunction "RD#_3") (pintype "input"))
    )
    (net (code "69") (name "RES0") (class "Default")
      (node (ref "U1") (pin "21") (pinfunction "PA1_21") (pintype "input"))
      (node (ref "U10") (pin "48") (pinfunction "RES0_48") (pintype "input"))
    )
    (net (code "70") (name "RES1") (class "Default")
      (node (ref "U1") (pin "20") (pinfunction "PA0_20") (pintype "input"))
      (node (ref "U10") (pin "1") (pinfunction "RES1_1") (pintype "input"))
    )
    (net (code "71") (name "RESET#") (class "Default")
      (node (ref "U1") (pin "2") (pinfunction "PE3_2") (pintype "input"))
      (node (ref "U10") (pin "33") (pinfunction "RESET#_33") (pintype "input"))
    )
    (net (code "72") (name "RX") (class "Default")
      (node (ref "H2") (pin "2") (pinfunction "2_2") (pintype "input"))
      (node (ref "U1") (pin "94") (pinfunction "PB7_94") (pintype "input"))
    )
    (net (code "73") (name "SAMPLE#") (class "Default")
      (node (ref "U1") (pin "10") (pinfunction "PF9_10") (pintype "input"))
      (node (ref "U10") (pin "10") (pinfunction "SAMPLE#_10") (pintype "input"))
    )
    (net (code "74") (name "SIN") (class "Default")
      (node (ref "C84") (pin "1") (pinfunction "1_1") (pintype "unspecified"))
      (node (ref "R67") (pin "2") (pinfunction "2_2") (pintype "input"))
      (node (ref "U10") (pin "41") (pinfunction "SIN_41") (pintype "input"))
      (node (ref "U26") (pin "1") (pinfunction "OUT_A_1") (pintype "output"))
    )
    (net (code "75") (name "SINLO") (class "Default")
      (node (ref "C69") (pin "1") (pinfunction "1_1") (pintype "unspecified"))
      (node (ref "R55") (pin "2") (pinfunction "2_2") (pintype "input"))
      (node (ref "U10") (pin "42") (pinfunction "SINLO_42") (pintype "input"))
      (node (ref "U26") (pin "7") (pinfunction "OUT_B_7") (pintype "output"))
    )
    (net (code "76") (name "SOE#") (class "Default")
      (node (ref "U1") (pin "11") (pinfunction "PF10_11") (pintype "input"))
      (node (ref "U10") (pin "9") (pinfunction "SOE#_9") (pintype "input"))
    )
    (net (code "77") (name "SWCLK") (class "Default")
      (node (ref "H1") (pin "3") (pinfunction "3_3") (pintype "input"))
      (node (ref "U1") (pin "77") (pinfunction "PA14_77") (pintype "input"))
    )
    (net (code "78") (name "SWDIO") (class "Default")
      (node (ref "H1") (pin "2") (pinfunction "2_2") (pintype "input"))
      (node (ref "U1") (pin "76") (pinfunction "PA13_76") (pintype "input"))
    )
    (net (code "79") (name "TX") (class "Default")
      (node (ref "H2") (pin "1") (pinfunction "1_1") (pintype "input"))
      (node (ref "U1") (pin "93") (pinfunction "PB6_93") (pintype "input"))
    )
    (net (code "80") (name "VREF") (class "Default")
      (node (ref "C57") (pin "2") (pinfunction "2_2") (pintype "unspecified"))
      (node (ref "C71") (pin "2") (pinfunction "2_2") (pintype "unspecified"))
      (node (ref "C74") (pin "2") (pinfunction "2_2") (pintype "unspecified"))
      (node (ref "C80") (pin "2") (pinfunction "2_2") (pintype "unspecified"))
      (node (ref "U10") (pin "47") (pinfunction "REFOUT_47") (pintype "input"))
      (node (ref "U25") (pin "10") (pinfunction "+IN_C_10") (pintype "input"))
      (node (ref "U25") (pin "12") (pinfunction "+IN_D_12") (pintype "input"))
      (node (ref "U25") (pin "3") (pinfunction "+IN_A_3") (pintype "input"))
      (node (ref "U25") (pin "5") (pinfunction "+IN_B_5") (pintype "input"))
      (node (ref "U26") (pin "10") (pinfunction "+IN_C_10") (pintype "input"))
      (node (ref "U26") (pin "12") (pinfunction "+IN_D_12") (pintype "input"))
      (node (ref "U26") (pin "3") (pinfunction "+IN_A_3") (pintype "input"))
      (node (ref "U26") (pin "5") (pinfunction "+IN_B_5") (pintype "input"))
      (node (ref "U27") (pin "3") (pinfunction "+IN_A_3") (pintype "input"))
      (node (ref "U27") (pin "5") (pinfunction "+IN_B_5") (pintype "input"))
    )
    (net (code "81") (name "WR#{slash}FSYNC#") (class "Default")
      (node (ref "U1") (pin "17") (pinfunction "PC2_17") (pintype "input"))
      (node (ref "U10") (pin "4") (pinfunction "WR#/FSYNC#_4") (pintype "input"))
    )
    (net (code "82") (name "unconnected-(U1-PA2-Pad22)") (class "Default")
      (node (ref "U1") (pin "22") (pinfunction "PA2_22") (pintype "input+no_connect"))
    )
    (net (code "83") (name "unconnected-(U1-PA3-Pad25)") (class "Default")
      (node (ref "U1") (pin "25") (pinfunction "PA3_25") (pintype "input+no_connect"))
    )
    (net (code "84") (name "unconnected-(U1-PA4-Pad26)") (class "Default")
      (node (ref "U1") (pin "26") (pinfunction "PA4_26") (pintype "input+no_connect"))
    )
    (net (code "85") (name "unconnected-(U1-PA5-Pad27)") (class "Default")
      (node (ref "U1") (pin "27") (pinfunction "PA5_27") (pintype "input+no_connect"))
    )
    (net (code "86") (name "unconnected-(U1-PA6-Pad28)") (class "Default")
      (node (ref "U1") (pin "28") (pinfunction "PA6_28") (pintype "input+no_connect"))
    )
    (net (code "87") (name "unconnected-(U1-PA7-Pad29)") (class "Default")
      (node (ref "U1") (pin "29") (pinfunction "PA7_29") (pintype "input+no_connect"))
    )
    (net (code "88") (name "unconnected-(U1-PA8-Pad69)") (class "Default")
      (node (ref "U1") (pin "69") (pinfunction "PA8_69") (pintype "input+no_connect"))
    )
    (net (code "89") (name "unconnected-(U1-PA9-Pad70)") (class "Default")
      (node (ref "U1") (pin "70") (pinfunction "PA9_70") (pintype "input+no_connect"))
    )
    (net (code "90") (name "unconnected-(U1-PA10-Pad71)") (class "Default")
      (node (ref "U1") (pin "71") (pinfunction "PA10_71") (pintype "input+no_connect"))
    )
    (net (code "91") (name "unconnected-(U1-PA15-Pad78)") (class "Default")
      (node (ref "U1") (pin "78") (pinfunction "PA15_78") (pintype "input+no_connect"))
    )
    (net (code "92") (name "unconnected-(U1-PB0-Pad32)") (class "Default")
      (node (ref "U1") (pin "32") (pinfunction "PB0_32") (pintype "input+no_connect"))
    )
    (net (code "93") (name "unconnected-(U1-PB1-Pad33)") (class "Default")
      (node (ref "U1") (pin "33") (pinfunction "PB1_33") (pintype "input+no_connect"))
    )
    (net (code "94") (name "unconnected-(U1-PB2-Pad34)") (class "Default")
      (node (ref "U1") (pin "34") (pinfunction "PB2_34") (pintype "input+no_connect"))
    )
    (net (code "95") (name "unconnected-(U1-PB3-Pad90)") (class "Default")
      (node (ref "U1") (pin "90") (pinfunction "PB3_90") (pintype "input+no_connect"))
    )
    (net (code "96") (name "unconnected-(U1-PB9-Pad96)") (class "Default")
      (node (ref "U1") (pin "96") (pinfunction "PB9_96") (pintype "input+no_connect"))
    )
    (net (code "97") (name "unconnected-(U1-PB10-Pad47)") (class "Default")
      (node (ref "U1") (pin "47") (pinfunction "PB10_47") (pintype "input+no_connect"))
    )
    (net (code "98") (name "unconnected-(U1-PB11-Pad50)") (class "Default")
      (node (ref "U1") (pin "50") (pinfunction "PB11_50") (pintype "input+no_connect"))
    )
    (net (code "99") (name "unconnected-(U1-PB12-Pad51)") (class "Default")
      (node (ref "U1") (pin "51") (pinfunction "PB12_51") (pintype "input+no_connect"))
    )
    (net (code "100") (name "unconnected-(U1-PB13-Pad52)") (class "Default")
      (node (ref "U1") (pin "52") (pinfunction "PB13_52") (pintype "input+no_connect"))
    )
    (net (code "101") (name "unconnected-(U1-PB14-Pad53)") (class "Default")
      (node (ref "U1") (pin "53") (pinfunction "PB14_53") (pintype "input+no_connect"))
    )
    (net (code "102") (name "unconnected-(U1-PB15-Pad54)") (class "Default")
      (node (ref "U1") (pin "54") (pinfunction "PB15_54") (pintype "input+no_connect"))
    )
    (net (code "103") (name "unconnected-(U1-PC0-Pad15)") (class "Default")
      (node (ref "U1") (pin "15") (pinfunction "PC0_15") (pintype "input+no_connect"))
    )
    (net (code "104") (name "unconnected-(U1-PC1-Pad16)") (class "Default")
      (node (ref "U1") (pin "16") (pinfunction "PC1_16") (pintype "input+no_connect"))
    )
    (net (code "105") (name "unconnected-(U1-PC4-Pad30)") (class "Default")
      (node (ref "U1") (pin "30") (pinfunction "PC4_30") (pintype "input+no_connect"))
    )
    (net (code "106") (name "unconnected-(U1-PC5-Pad31)") (class "Default")
      (node (ref "U1") (pin "31") (pinfunction "PC5_31") (pintype "input+no_connect"))
    )
    (net (code "107") (name "unconnected-(U1-PC6-Pad65)") (class "Default")
      (node (ref "U1") (pin "65") (pinfunction "PC6_65") (pintype "input+no_connect"))
    )
    (net (code "108") (name "unconnected-(U1-PC7-Pad66)") (class "Default")
      (node (ref "U1") (pin "66") (pinfunction "PC7_66") (pintype "input+no_connect"))
    )
    (net (code "109") (name "unconnected-(U1-PC8-Pad67)") (class "Default")
      (node (ref "U1") (pin "67") (pinfunction "PC8_67") (pintype "input+no_connect"))
    )
    (net (code "110") (name "unconnected-(U1-PC9-Pad68)") (class "Default")
      (node (ref "U1") (pin "68") (pinfunction "PC9_68") (pintype "input+no_connect"))
    )
    (net (code "111") (name "unconnected-(U1-PC10-Pad79)") (class "Default")
      (node (ref "U1") (pin "79") (pinfunction "PC10_79") (pintype "input+no_connect"))
    )
    (net (code "112") (name "unconnected-(U1-PC11-Pad80)") (class "Default")
      (node (ref "U1") (pin "80") (pinfunction "PC11_80") (pintype "input+no_connect"))
    )
    (net (code "113") (name "unconnected-(U1-PC12-Pad81)") (class "Default")
      (node (ref "U1") (pin "81") (pinfunction "PC12_81") (pintype "input+no_connect"))
    )
    (net (code "114") (name "unconnected-(U1-PC14-OSC32_IN-Pad8)") (class "Default")
      (node (ref "U1") (pin "8") (pinfunction "PC14-OSC32_IN_8") (pintype "input+no_connect"))
    )
    (net (code "115") (name "unconnected-(U1-PC15-OSC32_OUT-Pad9)") (class "Default")
      (node (ref "U1") (pin "9") (pinfunction "PC15-OSC32_OUT_9") (pintype "input+no_connect"))
    )
    (net (code "116") (name "unconnected-(U1-PD0-Pad82)") (class "Default")
      (node (ref "U1") (pin "82") (pinfunction "PD0_82") (pintype "input+no_connect"))
    )
    (net (code "117") (name "unconnected-(U1-PD1-Pad83)") (class "Default")
      (node (ref "U1") (pin "83") (pinfunction "PD1_83") (pintype "input+no_connect"))
    )
    (net (code "118") (name "unconnected-(U1-PD2-Pad84)") (class "Default")
      (node (ref "U1") (pin "84") (pinfunction "PD2_84") (pintype "input+no_connect"))
    )
    (net (code "119") (name "unconnected-(U1-PD3-Pad85)") (class "Default")
      (node (ref "U1") (pin "85") (pinfunction "PD3_85") (pintype "input+no_connect"))
    )
    (net (code "120") (name "unconnected-(U1-PD4-Pad86)") (class "Default")
      (node (ref "U1") (pin "86") (pinfunction "PD4_86") (pintype "input+no_connect"))
    )
    (net (code "121") (name "unconnected-(U1-PD5-Pad87)") (class "Default")
      (node (ref "U1") (pin "87") (pinfunction "PD5_87") (pintype "input+no_connect"))
    )
    (net (code "122") (name "unconnected-(U1-PD6-Pad88)") (class "Default")
      (node (ref "U1") (pin "88") (pinfunction "PD6_88") (pintype "input+no_connect"))
    )
    (net (code "123") (name "unconnected-(U1-PD7-Pad89)") (class "Default")
      (node (ref "U1") (pin "89") (pinfunction "PD7_89") (pintype "input+no_connect"))
    )
    (net (code "124") (name "unconnected-(U1-PD8-Pad55)") (class "Default")
      (node (ref "U1") (pin "55") (pinfunction "PD8_55") (pintype "input+no_connect"))
    )
    (net (code "125") (name "unconnected-(U1-PD9-Pad56)") (class "Default")
      (node (ref "U1") (pin "56") (pinfunction "PD9_56") (pintype "input+no_connect"))
    )
    (net (code "126") (name "unconnected-(U1-PD10-Pad57)") (class "Default")
      (node (ref "U1") (pin "57") (pinfunction "PD10_57") (pintype "input+no_connect"))
    )
    (net (code "127") (name "unconnected-(U1-PD11-Pad58)") (class "Default")
      (node (ref "U1") (pin "58") (pinfunction "PD11_58") (pintype "input+no_connect"))
    )
    (net (code "128") (name "unconnected-(U1-PD12-Pad59)") (class "Default")
      (node (ref "U1") (pin "59") (pinfunction "PD12_59") (pintype "input+no_connect"))
    )
    (net (code "129") (name "unconnected-(U1-PD13-Pad60)") (class "Default")
      (node (ref "U1") (pin "60") (pinfunction "PD13_60") (pintype "input+no_connect"))
    )
    (net (code "130") (name "unconnected-(U1-PD14-Pad61)") (class "Default")
      (node (ref "U1") (pin "61") (pinfunction "PD14_61") (pintype "input+no_connect"))
    )
    (net (code "131") (name "unconnected-(U1-PD15-Pad62)") (class "Default")
      (node (ref "U1") (pin "62") (pinfunction "PD15_62") (pintype "input+no_connect"))
    )
    (net (code "132") (name "unconnected-(U1-PE4-Pad3)") (class "Default")
      (node (ref "U1") (pin "3") (pinfunction "PE4_3") (pintype "input+no_connect"))
    )
    (net (code "133") (name "unconnected-(U1-PE7-Pad38)") (class "Default")
      (node (ref "U1") (pin "38") (pinfunction "PE7_38") (pintype "input+no_connect"))
    )
    (net (code "134") (name "unconnected-(U1-PE8-Pad39)") (class "Default")
      (node (ref "U1") (pin "39") (pinfunction "PE8_39") (pintype "input+no_connect"))
    )
    (net (code "135") (name "unconnected-(U1-PE9-Pad40)") (class "Default")
      (node (ref "U1") (pin "40") (pinfunction "PE9_40") (pintype "input+no_connect"))
    )
    (net (code "136") (name "unconnected-(U1-PE10-Pad41)") (class "Default")
      (node (ref "U1") (pin "41") (pinfunction "PE10_41") (pintype "input+no_connect"))
    )
    (net (code "137") (name "unconnected-(U1-PE11-Pad42)") (class "Default")
      (node (ref "U1") (pin "42") (pinfunction "PE11_42") (pintype "input+no_connect"))
    )
    (net (code "138") (name "unconnected-(U1-PE12-Pad43)") (class "Default")
      (node (ref "U1") (pin "43") (pinfunction "PE12_43") (pintype "input+no_connect"))
    )
    (net (code "139") (name "unconnected-(U1-PE13-Pad44)") (class "Default")
      (node (ref "U1") (pin "44") (pinfunction "PE13_44") (pintype "input+no_connect"))
    )
    (net (code "140") (name "unconnected-(U1-PE14-Pad45)") (class "Default")
      (node (ref "U1") (pin "45") (pinfunction "PE14_45") (pintype "input+no_connect"))
    )
    (net (code "141") (name "unconnected-(U1-PE15-Pad46)") (class "Default")
      (node (ref "U1") (pin "46") (pinfunction "PE15_46") (pintype "input+no_connect"))
    )
    (net (code "142") (name "unconnected-(U10-A-Pad29)") (class "Default")
      (node (ref "U10") (pin "29") (pinfunction "A_29") (pintype "input+no_connect"))
    )
    (net (code "143") (name "unconnected-(U10-B-Pad30)") (class "Default")
      (node (ref "U10") (pin "30") (pinfunction "B_30") (pintype "input+no_connect"))
    )
    (net (code "144") (name "unconnected-(U10-DB0-Pad28)") (class "Default")
      (node (ref "U10") (pin "28") (pinfunction "DB0_28") (pintype "input+no_connect"))
    )
    (net (code "145") (name "unconnected-(U10-DB1-Pad27)") (class "Default")
      (node (ref "U10") (pin "27") (pinfunction "DB1_27") (pintype "input+no_connect"))
    )
    (net (code "146") (name "unconnected-(U10-DB2-Pad26)") (class "Default")
      (node (ref "U10") (pin "26") (pinfunction "DB2_26") (pintype "input+no_connect"))
    )
    (net (code "147") (name "unconnected-(U10-DB3-Pad25)") (class "Default")
      (node (ref "U10") (pin "25") (pinfunction "DB3_25") (pintype "input+no_connect"))
    )
    (net (code "148") (name "unconnected-(U10-DB4-Pad24)") (class "Default")
      (node (ref "U10") (pin "24") (pinfunction "DB4_24") (pintype "input+no_connect"))
    )
    (net (code "149") (name "unconnected-(U10-DB5-Pad23)") (class "Default")
      (node (ref "U10") (pin "23") (pinfunction "DB5_23") (pintype "input+no_connect"))
    )
    (net (code "150") (name "unconnected-(U10-DB6-Pad22)") (class "Default")
      (node (ref "U10") (pin "22") (pinfunction "DB6_22") (pintype "input+no_connect"))
    )
    (net (code "151") (name "unconnected-(U10-DB7-Pad21)") (class "Default")
      (node (ref "U10") (pin "21") (pinfunction "DB7_21") (pintype "input+no_connect"))
    )
    (net (code "152") (name "unconnected-(U10-DB8-Pad20)") (class "Default")
      (node (ref "U10") (pin "20") (pinfunction "DB8_20") (pintype "input+no_connect"))
    )
    (net (code "153") (name "unconnected-(U10-DB9-Pad17)") (class "Default")
      (node (ref "U10") (pin "17") (pinfunction "DB9_17") (pintype "input+no_connect"))
    )
    (net (code "154") (name "unconnected-(U10-DB10-Pad16)") (class "Default")
      (node (ref "U10") (pin "16") (pinfunction "DB10_16") (pintype "input+no_connect"))
    )
    (net (code "155") (name "unconnected-(U10-DB11-Pad15)") (class "Default")
      (node (ref "U10") (pin "15") (pinfunction "DB11_15") (pintype "input+no_connect"))
    )
    (net (code "156") (name "unconnected-(U10-DB12-Pad14)") (class "Default")
      (node (ref "U10") (pin "14") (pinfunction "DB12_14") (pintype "input+no_connect"))
    )
    (net (code "157") (name "unconnected-(U10-NM-Pad31)") (class "Default")
      (node (ref "U10") (pin "31") (pinfunction "NM_31") (pintype "input+no_connect"))
    )
  )
)
